# untitled.net
KiCad netlist of a schematic drawn in EAGLE
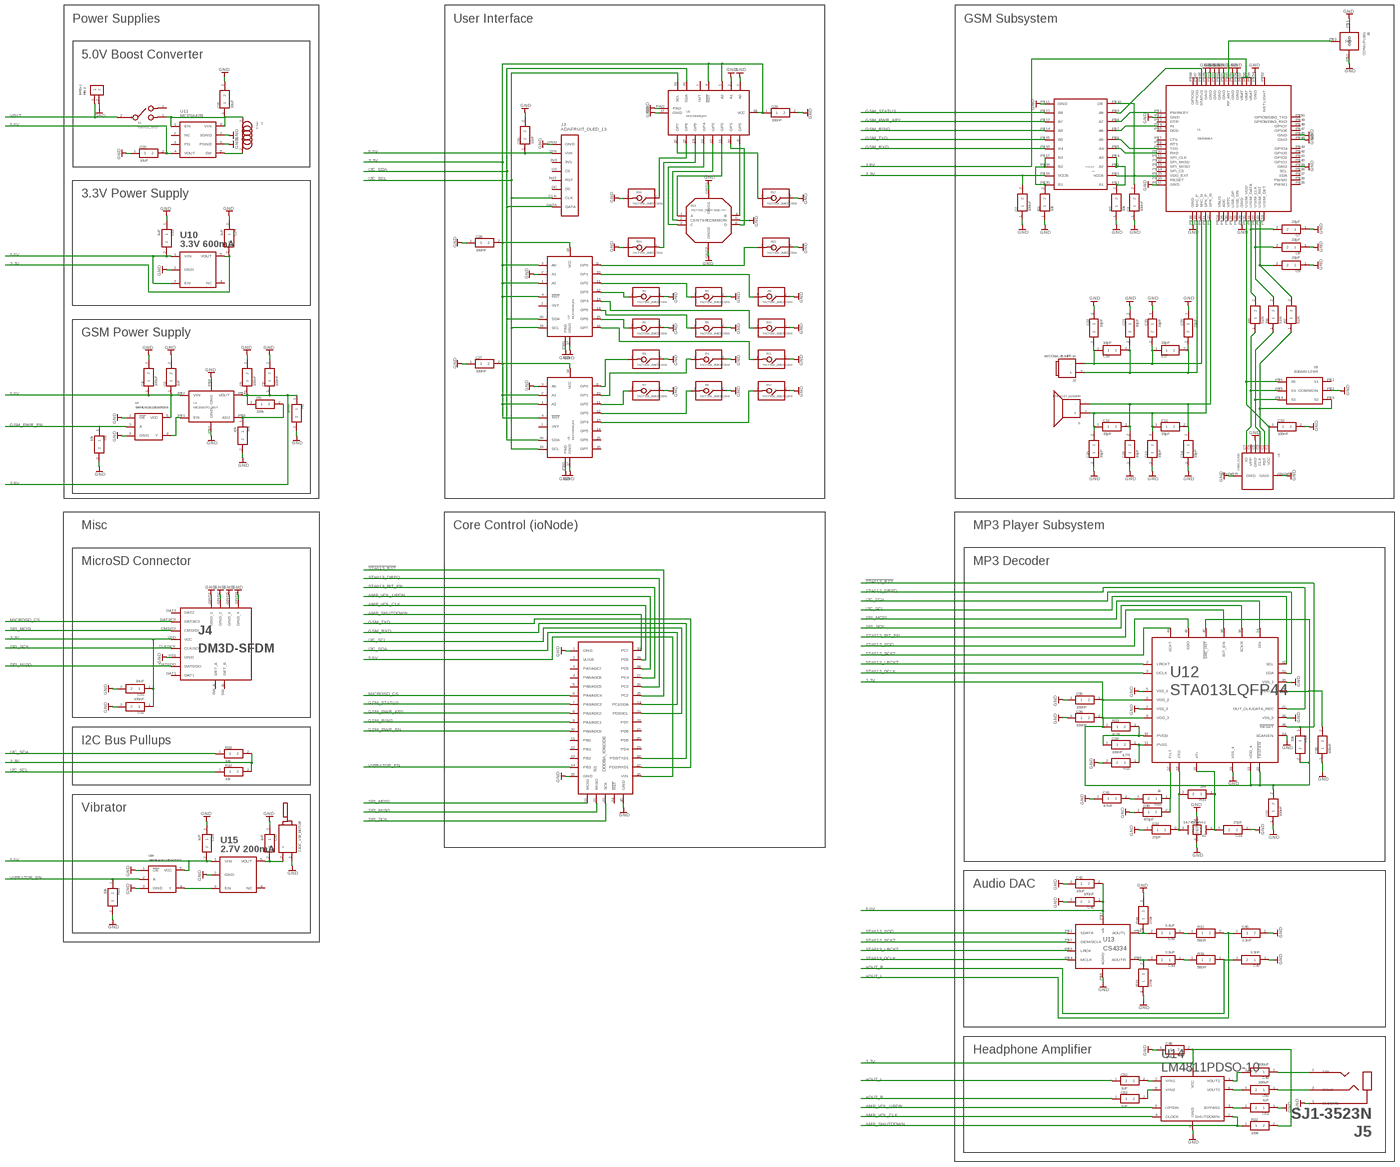
[diagram p0: schematic, sheet 1, overview]
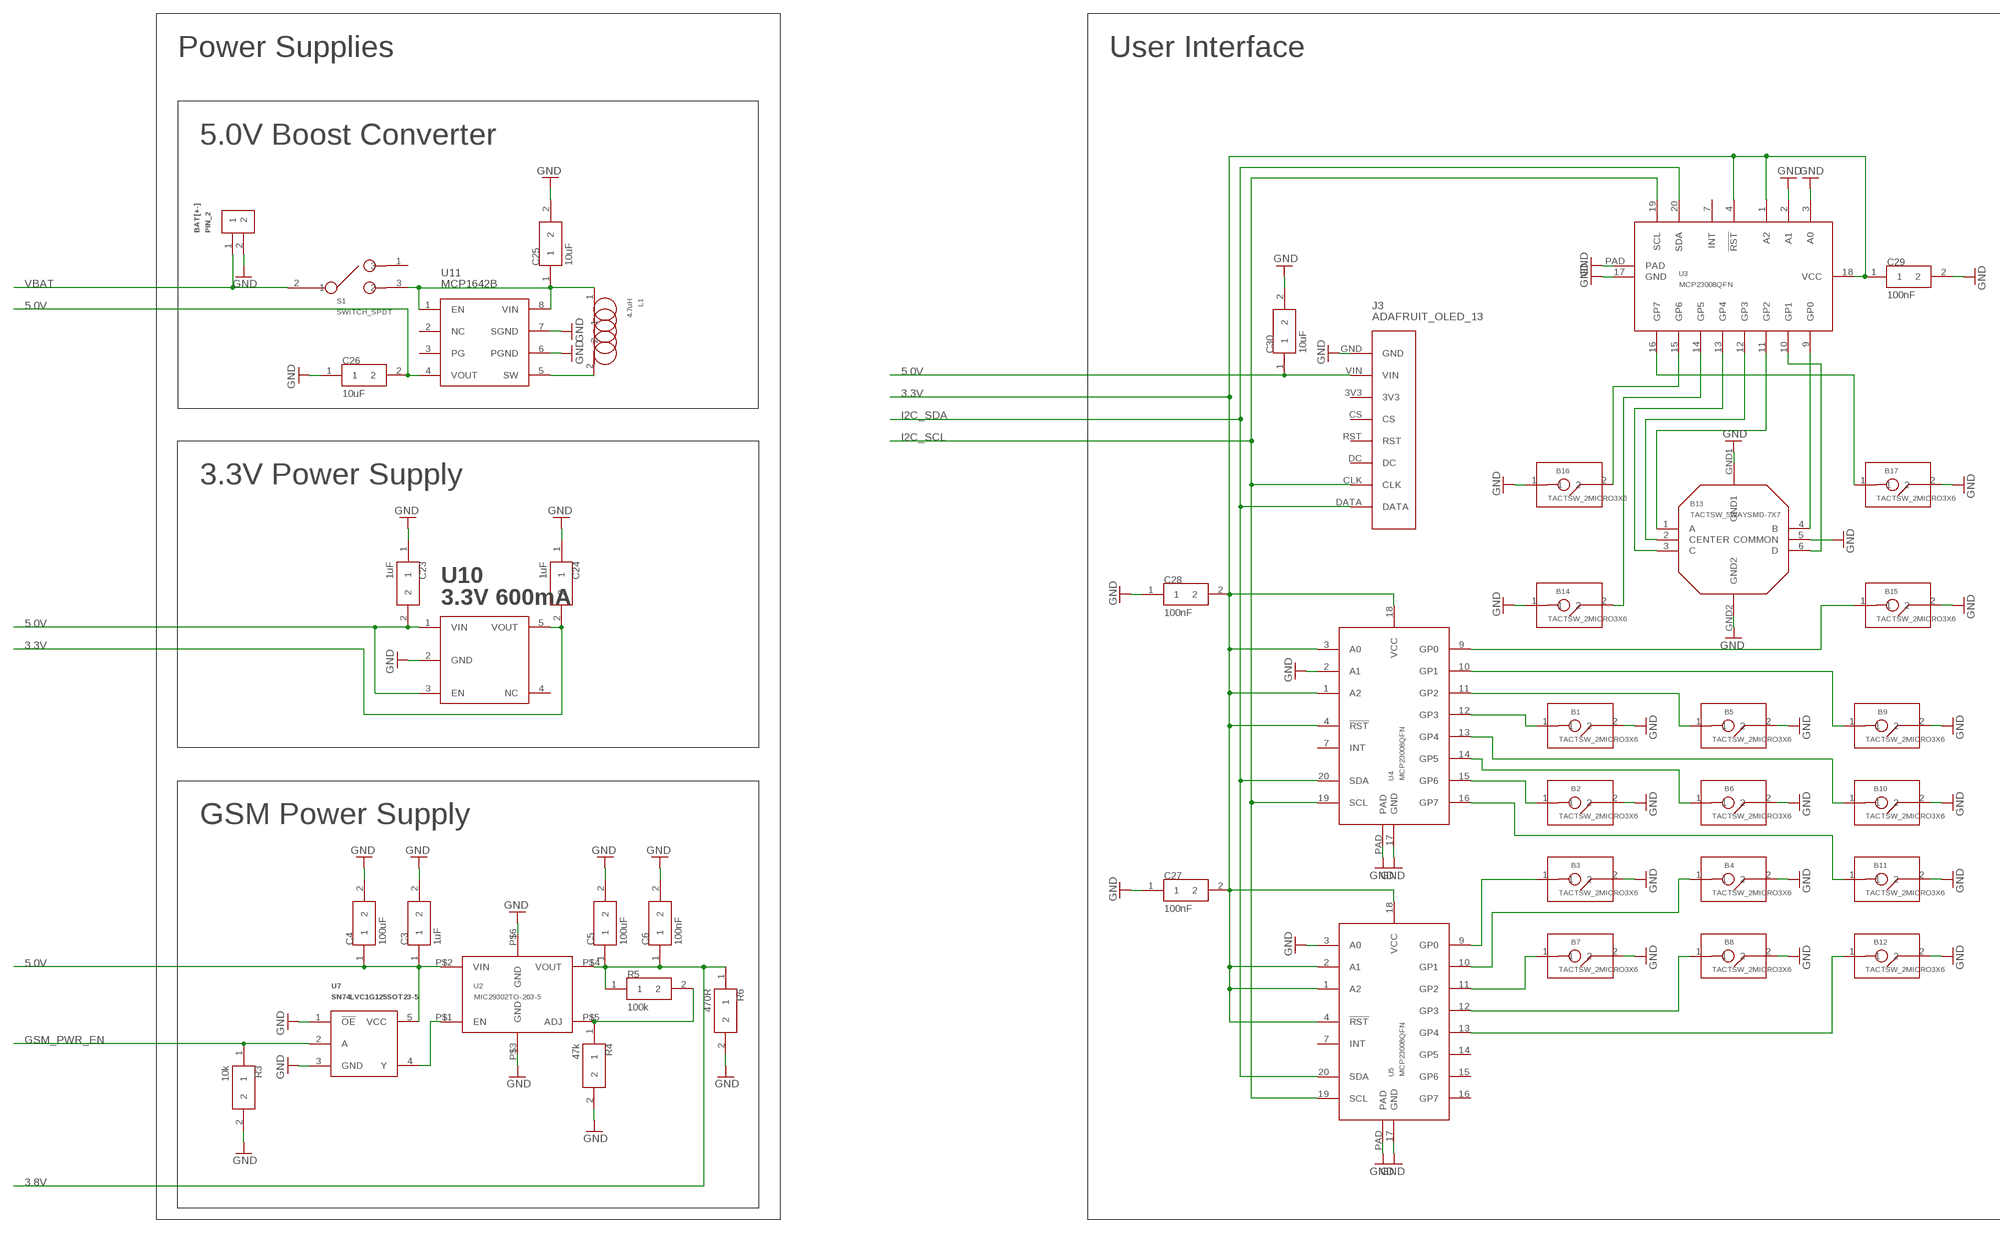
[diagram p1: schematic, sheet 1, part 1 of 4]
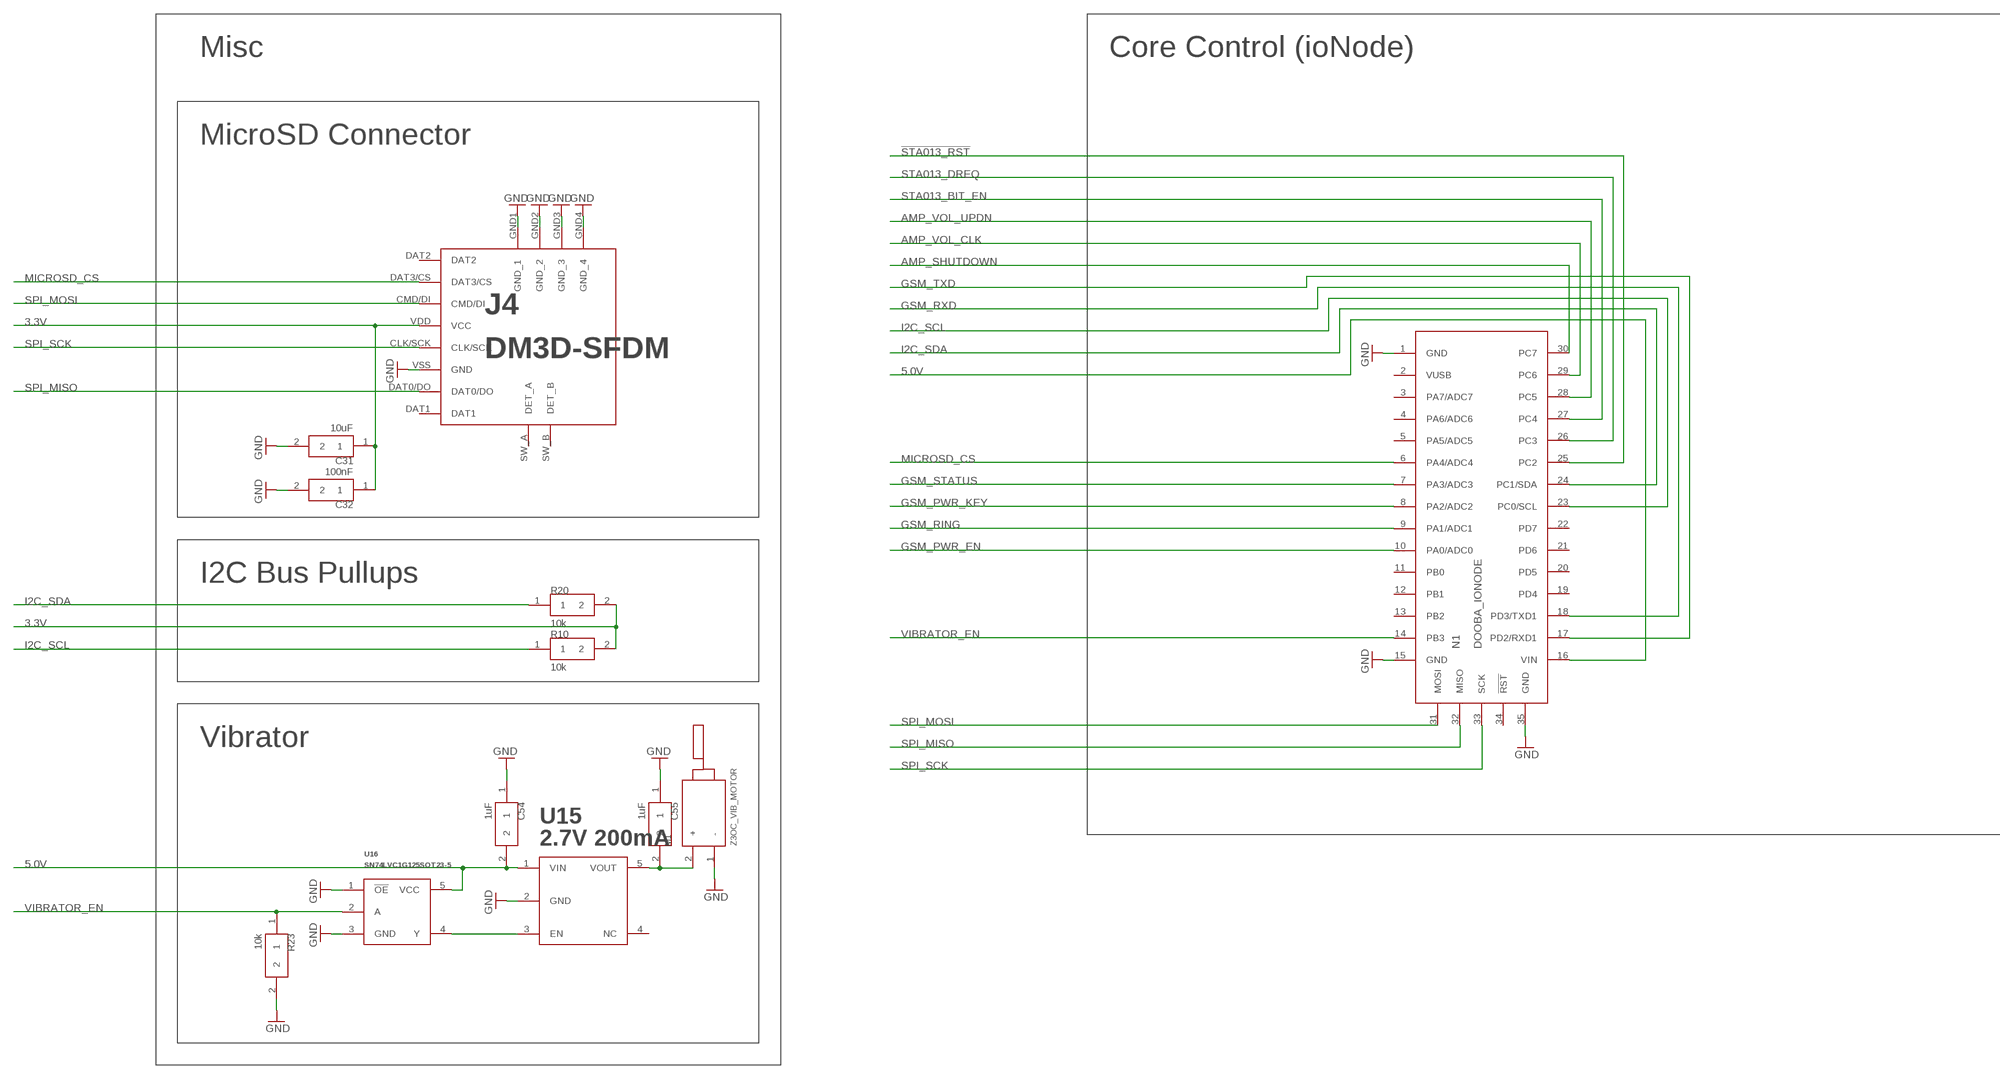
[diagram p2: schematic, sheet 1, part 2 of 4]
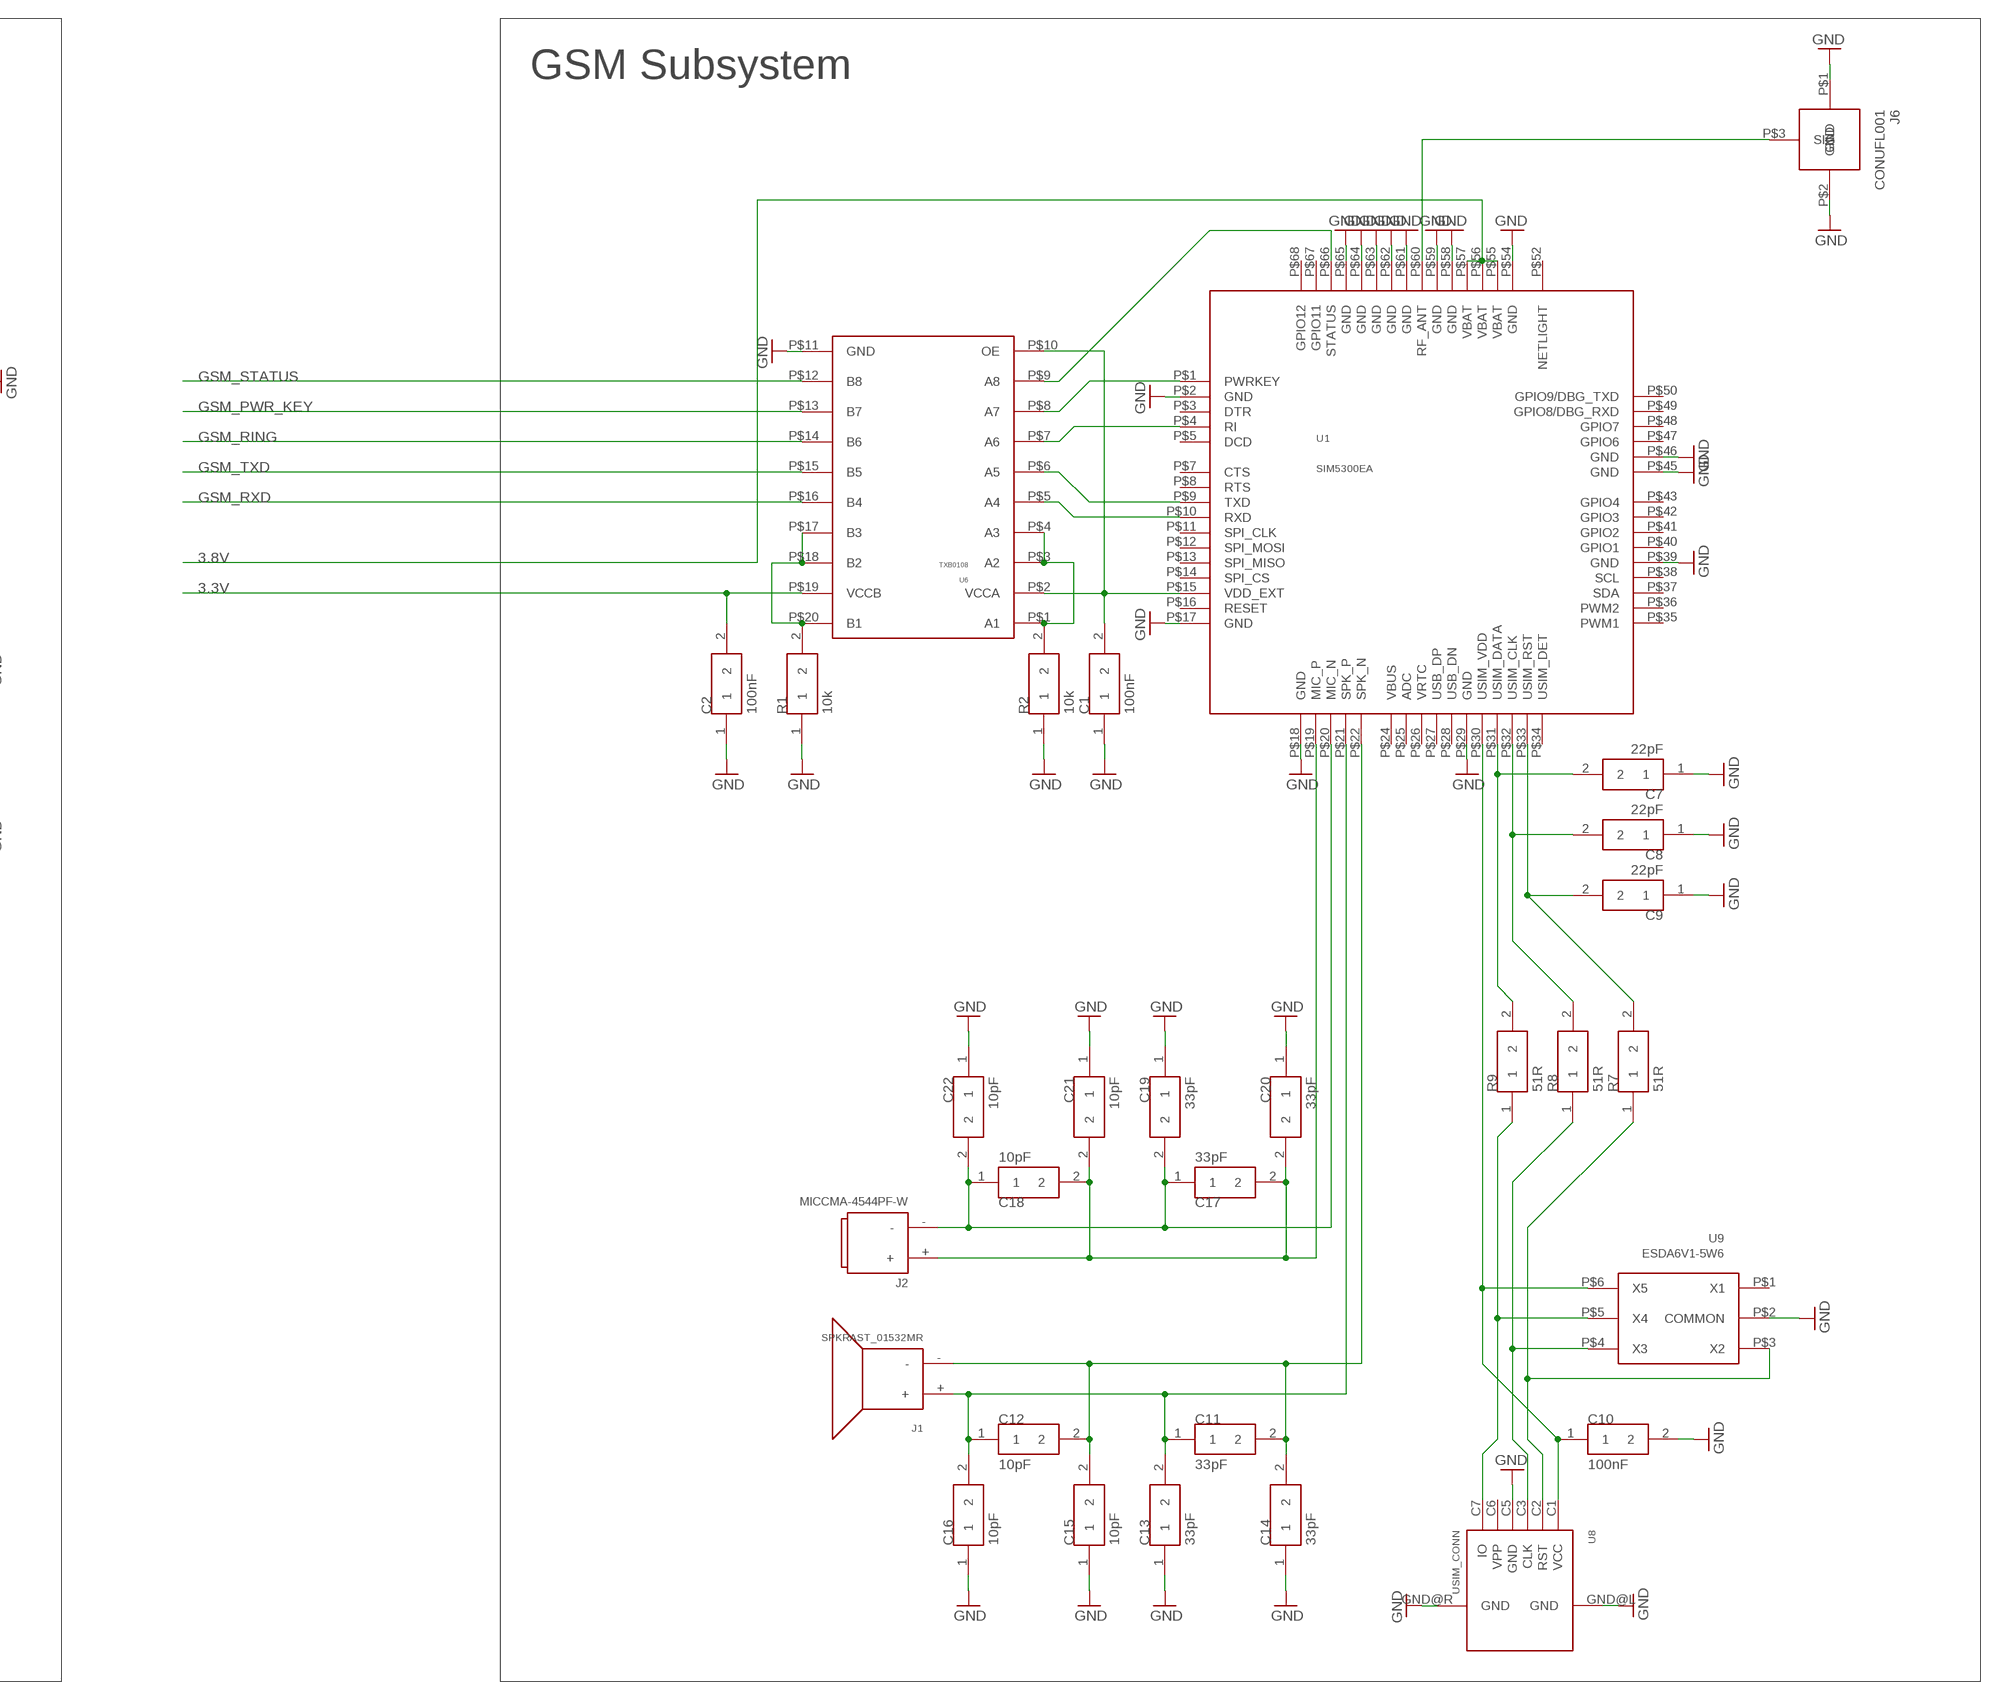
[diagram p3: schematic, sheet 1, part 3 of 4]
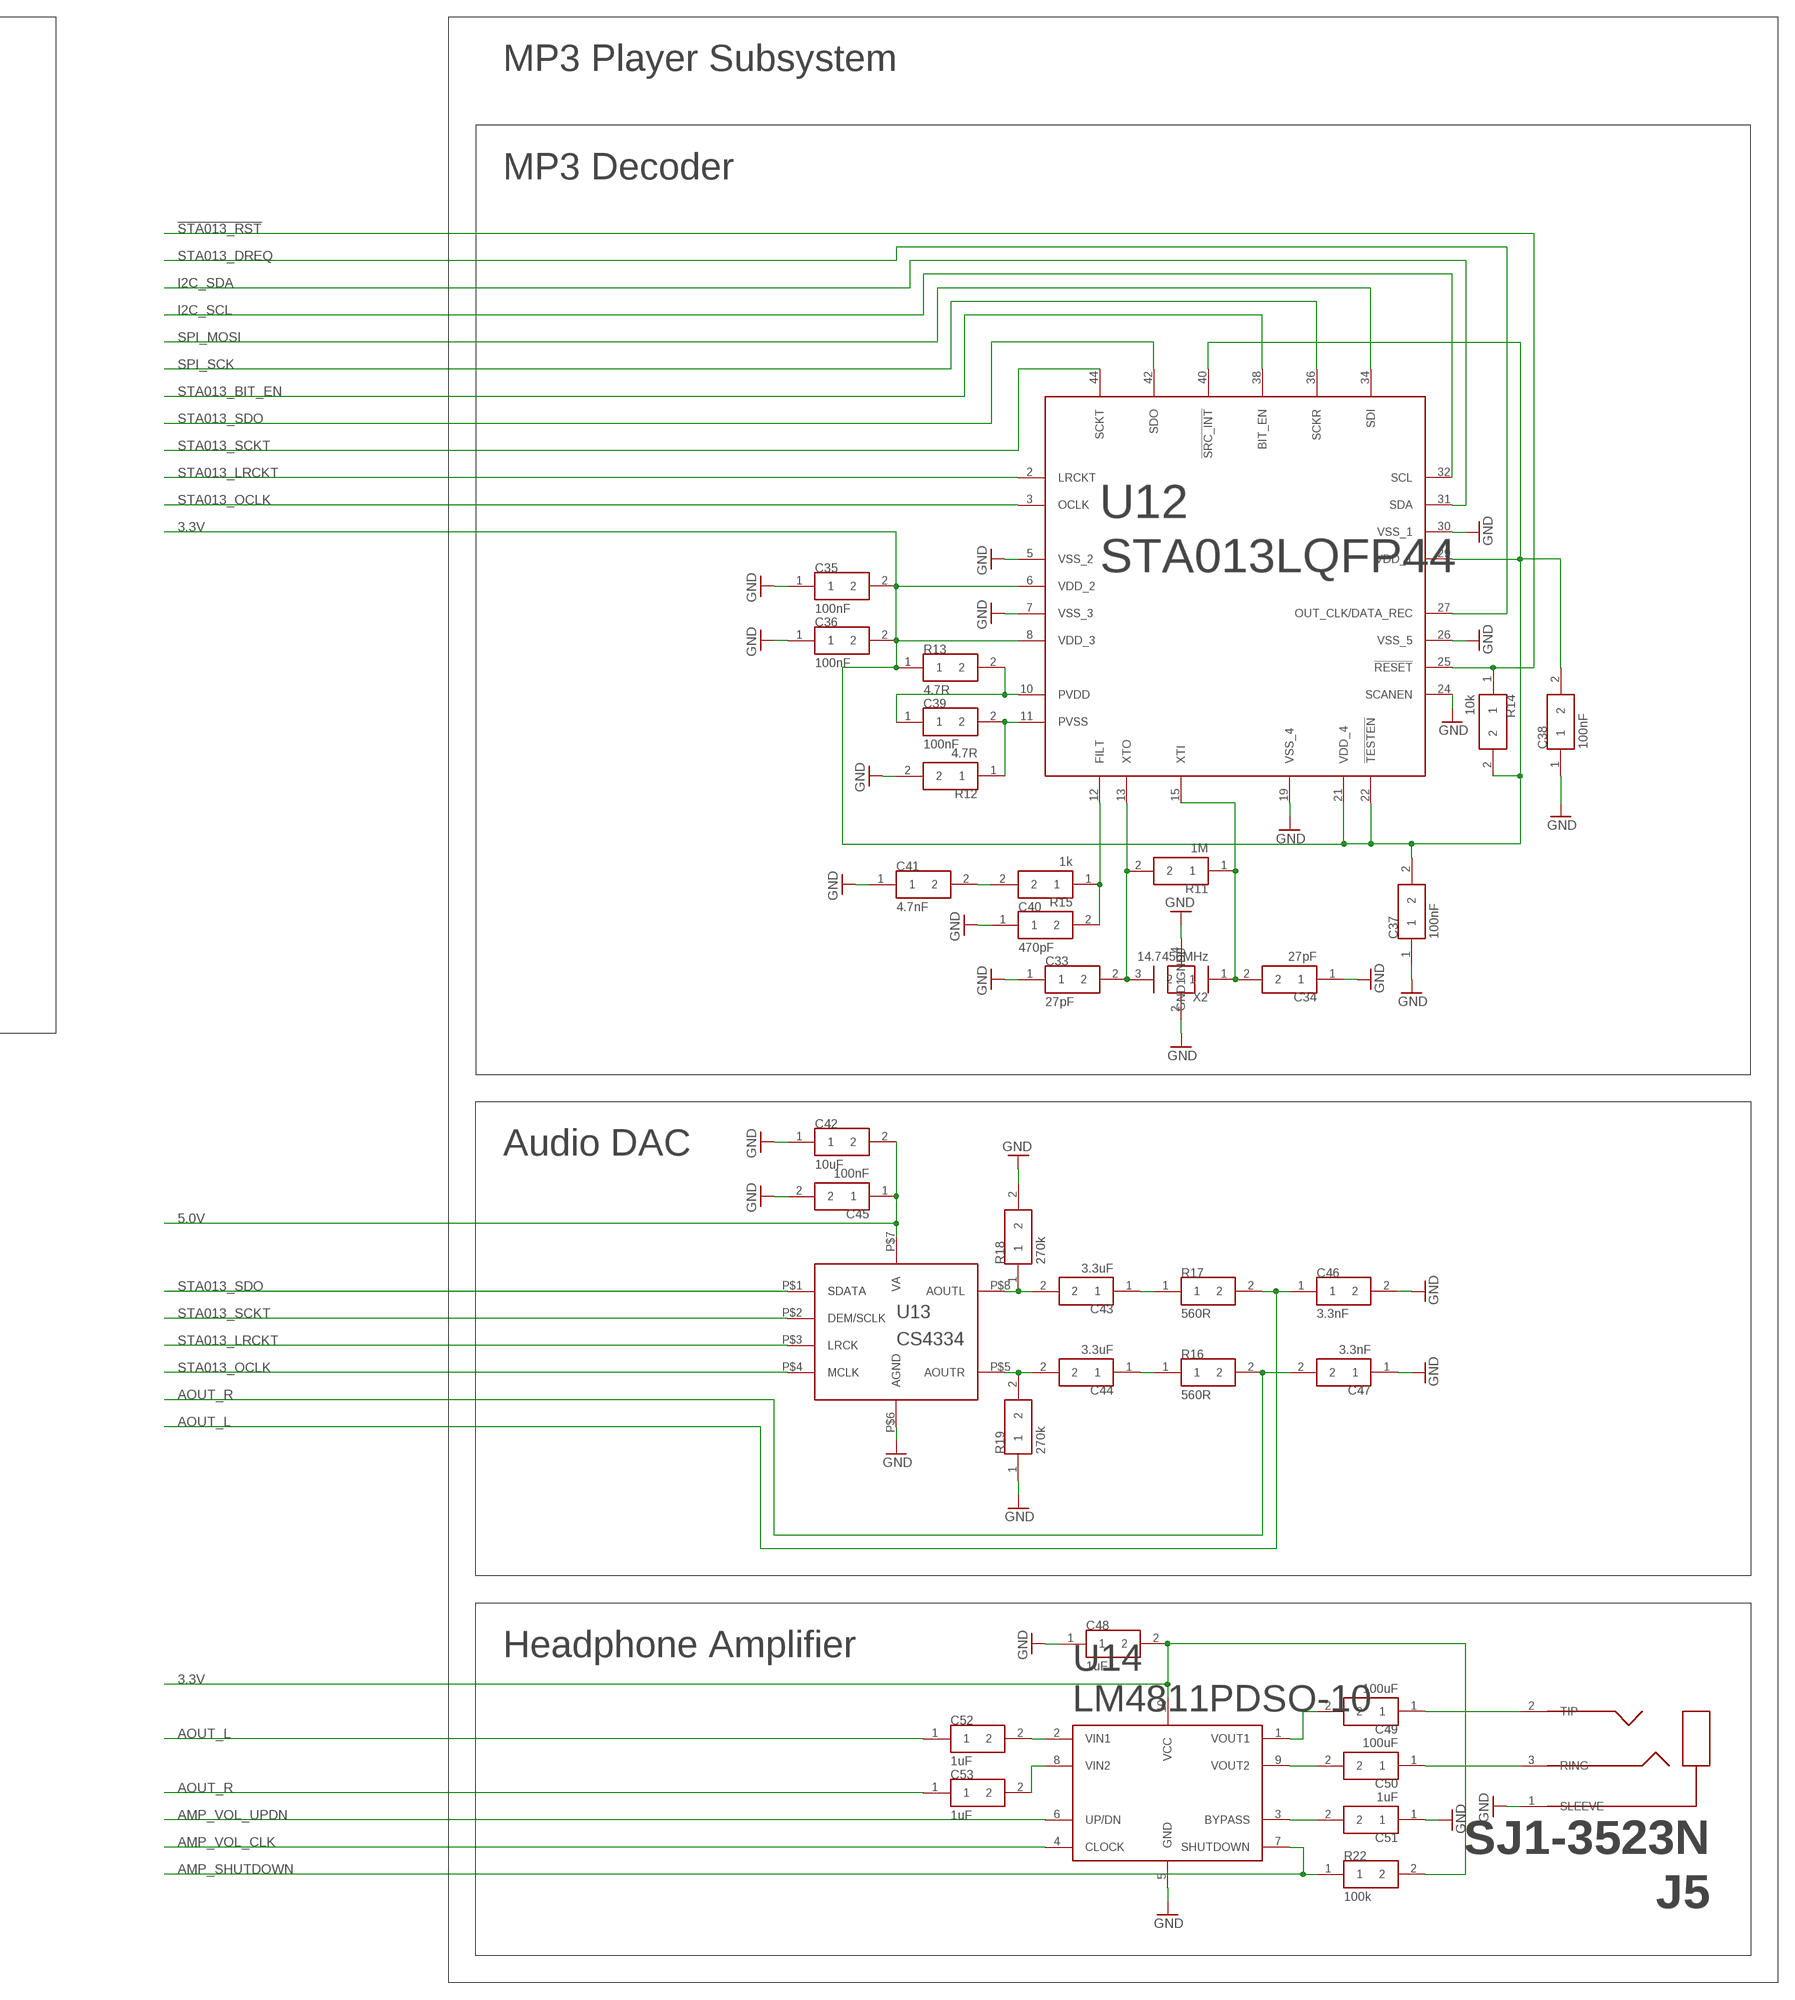
[diagram p4: schematic, sheet 1, part 4 of 4]

(export (version "E")
  (design (tool "Eeschema 10.0.6"))
  (components
    (comp (ref "B1")
      (value "TACTSW_2MICRO3X6")
      (footprint "eagle-import:TACTSW_MICRO3X6")
      (libsource (lib "eagle-import") (part "TACTSW_2MICRO3X6"))
    )
    (comp (ref "B2")
      (value "TACTSW_2MICRO3X6")
      (footprint "eagle-import:TACTSW_MICRO3X6")
      (libsource (lib "eagle-import") (part "TACTSW_2MICRO3X6"))
    )
    (comp (ref "B3")
      (value "TACTSW_2MICRO3X6")
      (footprint "eagle-import:TACTSW_MICRO3X6")
      (libsource (lib "eagle-import") (part "TACTSW_2MICRO3X6"))
    )
    (comp (ref "B4")
      (value "TACTSW_2MICRO3X6")
      (footprint "eagle-import:TACTSW_MICRO3X6")
      (libsource (lib "eagle-import") (part "TACTSW_2MICRO3X6"))
    )
    (comp (ref "B5")
      (value "TACTSW_2MICRO3X6")
      (footprint "eagle-import:TACTSW_MICRO3X6")
      (libsource (lib "eagle-import") (part "TACTSW_2MICRO3X6"))
    )
    (comp (ref "B6")
      (value "TACTSW_2MICRO3X6")
      (footprint "eagle-import:TACTSW_MICRO3X6")
      (libsource (lib "eagle-import") (part "TACTSW_2MICRO3X6"))
    )
    (comp (ref "B7")
      (value "TACTSW_2MICRO3X6")
      (footprint "eagle-import:TACTSW_MICRO3X6")
      (libsource (lib "eagle-import") (part "TACTSW_2MICRO3X6"))
    )
    (comp (ref "B8")
      (value "TACTSW_2MICRO3X6")
      (footprint "eagle-import:TACTSW_MICRO3X6")
      (libsource (lib "eagle-import") (part "TACTSW_2MICRO3X6"))
    )
    (comp (ref "B9")
      (value "TACTSW_2MICRO3X6")
      (footprint "eagle-import:TACTSW_MICRO3X6")
      (libsource (lib "eagle-import") (part "TACTSW_2MICRO3X6"))
    )
    (comp (ref "B10")
      (value "TACTSW_2MICRO3X6")
      (footprint "eagle-import:TACTSW_MICRO3X6")
      (libsource (lib "eagle-import") (part "TACTSW_2MICRO3X6"))
    )
    (comp (ref "B11")
      (value "TACTSW_2MICRO3X6")
      (footprint "eagle-import:TACTSW_MICRO3X6")
      (libsource (lib "eagle-import") (part "TACTSW_2MICRO3X6"))
    )
    (comp (ref "B12")
      (value "TACTSW_2MICRO3X6")
      (footprint "eagle-import:TACTSW_MICRO3X6")
      (libsource (lib "eagle-import") (part "TACTSW_2MICRO3X6"))
    )
    (comp (ref "B13")
      (value "TACTSW_5WAYSMD-7X7")
      (footprint "eagle-import:TACTSW-5WAY-7X7")
      (libsource (lib "eagle-import") (part "TACTSW_5WAYSMD-7X7"))
    )
    (comp (ref "B14")
      (value "TACTSW_2MICRO3X6")
      (footprint "eagle-import:TACTSW_MICRO3X6")
      (libsource (lib "eagle-import") (part "TACTSW_2MICRO3X6"))
    )
    (comp (ref "B15")
      (value "TACTSW_2MICRO3X6")
      (footprint "eagle-import:TACTSW_MICRO3X6")
      (libsource (lib "eagle-import") (part "TACTSW_2MICRO3X6"))
    )
    (comp (ref "B16")
      (value "TACTSW_2MICRO3X6")
      (footprint "eagle-import:TACTSW_MICRO3X6")
      (libsource (lib "eagle-import") (part "TACTSW_2MICRO3X6"))
    )
    (comp (ref "B17")
      (value "TACTSW_2MICRO3X6")
      (footprint "eagle-import:TACTSW_MICRO3X6")
      (libsource (lib "eagle-import") (part "TACTSW_2MICRO3X6"))
    )
    (comp (ref "BAT[+-]")
      (value "PIN_2")
      (footprint "eagle-import:PIN_2")
      (libsource (lib "eagle-import") (part "PIN_2"))
    )
    (comp (ref "C1")
      (value "100nF")
      (footprint "eagle-import:0805")
      (libsource (lib "eagle-import") (part "CAP0805"))
    )
    (comp (ref "C2")
      (value "100nF")
      (footprint "eagle-import:0805")
      (libsource (lib "eagle-import") (part "CAP0805"))
    )
    (comp (ref "C3")
      (value "1uF")
      (footprint "eagle-import:0805")
      (libsource (lib "eagle-import") (part "CAP0805"))
    )
    (comp (ref "C4")
      (value "100uF")
      (footprint "eagle-import:1210")
      (libsource (lib "eagle-import") (part "CAP1210"))
    )
    (comp (ref "C5")
      (value "100uF")
      (footprint "eagle-import:1210")
      (libsource (lib "eagle-import") (part "CAP1210"))
    )
    (comp (ref "C6")
      (value "100nF")
      (footprint "eagle-import:0805")
      (libsource (lib "eagle-import") (part "CAP0805"))
    )
    (comp (ref "C7")
      (value "22pF")
      (footprint "eagle-import:0805")
      (libsource (lib "eagle-import") (part "CAP0805"))
    )
    (comp (ref "C8")
      (value "22pF")
      (footprint "eagle-import:0805")
      (libsource (lib "eagle-import") (part "CAP0805"))
    )
    (comp (ref "C9")
      (value "22pF")
      (footprint "eagle-import:0805")
      (libsource (lib "eagle-import") (part "CAP0805"))
    )
    (comp (ref "C10")
      (value "100nF")
      (footprint "eagle-import:0805")
      (libsource (lib "eagle-import") (part "CAP0805"))
    )
    (comp (ref "C11")
      (value "33pF")
      (footprint "eagle-import:0805")
      (libsource (lib "eagle-import") (part "CAP0805"))
    )
    (comp (ref "C12")
      (value "10pF")
      (footprint "eagle-import:0805")
      (libsource (lib "eagle-import") (part "CAP0805"))
    )
    (comp (ref "C13")
      (value "33pF")
      (footprint "eagle-import:0805")
      (libsource (lib "eagle-import") (part "CAP0805"))
    )
    (comp (ref "C14")
      (value "33pF")
      (footprint "eagle-import:0805")
      (libsource (lib "eagle-import") (part "CAP0805"))
    )
    (comp (ref "C15")
      (value "10pF")
      (footprint "eagle-import:0805")
      (libsource (lib "eagle-import") (part "CAP0805"))
    )
    (comp (ref "C16")
      (value "10pF")
      (footprint "eagle-import:0805")
      (libsource (lib "eagle-import") (part "CAP0805"))
    )
    (comp (ref "C17")
      (value "33pF")
      (footprint "eagle-import:0805")
      (libsource (lib "eagle-import") (part "CAP0805"))
    )
    (comp (ref "C18")
      (value "10pF")
      (footprint "eagle-import:0805")
      (libsource (lib "eagle-import") (part "CAP0805"))
    )
    (comp (ref "C19")
      (value "33pF")
      (footprint "eagle-import:0805")
      (libsource (lib "eagle-import") (part "CAP0805"))
    )
    (comp (ref "C20")
      (value "33pF")
      (footprint "eagle-import:0805")
      (libsource (lib "eagle-import") (part "CAP0805"))
    )
    (comp (ref "C21")
      (value "10pF")
      (footprint "eagle-import:0805")
      (libsource (lib "eagle-import") (part "CAP0805"))
    )
    (comp (ref "C22")
      (value "10pF")
      (footprint "eagle-import:0805")
      (libsource (lib "eagle-import") (part "CAP0805"))
    )
    (comp (ref "C23")
      (value "1uF")
      (footprint "eagle-import:0805")
      (libsource (lib "eagle-import") (part "CAP0805"))
    )
    (comp (ref "C24")
      (value "1uF")
      (footprint "eagle-import:0805")
      (libsource (lib "eagle-import") (part "CAP0805"))
    )
    (comp (ref "C25")
      (value "10uF")
      (footprint "eagle-import:0805")
      (libsource (lib "eagle-import") (part "CAP0805"))
    )
    (comp (ref "C26")
      (value "10uF")
      (footprint "eagle-import:0805")
      (libsource (lib "eagle-import") (part "CAP0805"))
    )
    (comp (ref "C27")
      (value "100nF")
      (footprint "eagle-import:0805")
      (libsource (lib "eagle-import") (part "CAP0805"))
    )
    (comp (ref "C28")
      (value "100nF")
      (footprint "eagle-import:0805")
      (libsource (lib "eagle-import") (part "CAP0805"))
    )
    (comp (ref "C29")
      (value "100nF")
      (footprint "eagle-import:0805")
      (libsource (lib "eagle-import") (part "CAP0805"))
    )
    (comp (ref "C30")
      (value "10uF")
      (footprint "eagle-import:0805")
      (libsource (lib "eagle-import") (part "CAP0805"))
    )
    (comp (ref "C31")
      (value "10uF")
      (footprint "eagle-import:0805")
      (libsource (lib "eagle-import") (part "CAP0805"))
    )
    (comp (ref "C32")
      (value "100nF")
      (footprint "eagle-import:0805")
      (libsource (lib "eagle-import") (part "CAP0805"))
    )
    (comp (ref "C33")
      (value "27pF")
      (footprint "eagle-import:0805")
      (libsource (lib "eagle-import") (part "CAP0805"))
    )
    (comp (ref "C34")
      (value "27pF")
      (footprint "eagle-import:0805")
      (libsource (lib "eagle-import") (part "CAP0805"))
    )
    (comp (ref "C35")
      (value "100nF")
      (footprint "eagle-import:0805")
      (libsource (lib "eagle-import") (part "CAP0805"))
    )
    (comp (ref "C36")
      (value "100nF")
      (footprint "eagle-import:0805")
      (libsource (lib "eagle-import") (part "CAP0805"))
    )
    (comp (ref "C37")
      (value "100nF")
      (footprint "eagle-import:0805")
      (libsource (lib "eagle-import") (part "CAP0805"))
    )
    (comp (ref "C38")
      (value "100nF")
      (footprint "eagle-import:0805")
      (libsource (lib "eagle-import") (part "CAP0805"))
    )
    (comp (ref "C39")
      (value "100nF")
      (footprint "eagle-import:0805")
      (libsource (lib "eagle-import") (part "CAP0805"))
    )
    (comp (ref "C40")
      (value "470pF")
      (footprint "eagle-import:0805")
      (libsource (lib "eagle-import") (part "CAP0805"))
    )
    (comp (ref "C41")
      (value "4.7nF")
      (footprint "eagle-import:0805")
      (libsource (lib "eagle-import") (part "CAP0805"))
    )
    (comp (ref "C42")
      (value "10uF")
      (footprint "eagle-import:0805")
      (libsource (lib "eagle-import") (part "CAP0805"))
    )
    (comp (ref "C43")
      (value "3.3uF")
      (footprint "eagle-import:0805")
      (libsource (lib "eagle-import") (part "CAP0805"))
    )
    (comp (ref "C44")
      (value "3.3uF")
      (footprint "eagle-import:0805")
      (libsource (lib "eagle-import") (part "CAP0805"))
    )
    (comp (ref "C45")
      (value "100nF")
      (footprint "eagle-import:0805")
      (libsource (lib "eagle-import") (part "CAP0805"))
    )
    (comp (ref "C46")
      (value "3.3nF")
      (footprint "eagle-import:0805")
      (libsource (lib "eagle-import") (part "CAP0805"))
    )
    (comp (ref "C47")
      (value "3.3nF")
      (footprint "eagle-import:0805")
      (libsource (lib "eagle-import") (part "CAP0805"))
    )
    (comp (ref "C48")
      (value "1uF")
      (footprint "eagle-import:0805")
      (libsource (lib "eagle-import") (part "CAP0805"))
    )
    (comp (ref "C49")
      (value "100uF")
      (footprint "eagle-import:1210")
      (libsource (lib "eagle-import") (part "CAP1210"))
    )
    (comp (ref "C50")
      (value "100uF")
      (footprint "eagle-import:1210")
      (libsource (lib "eagle-import") (part "CAP1210"))
    )
    (comp (ref "C51")
      (value "1uF")
      (footprint "eagle-import:0805")
      (libsource (lib "eagle-import") (part "CAP0805"))
    )
    (comp (ref "C52")
      (value "1uF")
      (footprint "eagle-import:0805")
      (libsource (lib "eagle-import") (part "CAP0805"))
    )
    (comp (ref "C53")
      (value "1uF")
      (footprint "eagle-import:0805")
      (libsource (lib "eagle-import") (part "CAP0805"))
    )
    (comp (ref "C54")
      (value "1uF")
      (footprint "eagle-import:0805")
      (libsource (lib "eagle-import") (part "CAP0805"))
    )
    (comp (ref "C55")
      (value "1uF")
      (footprint "eagle-import:0805")
      (libsource (lib "eagle-import") (part "CAP0805"))
    )
    (comp (ref "J1")
      (value "SPKRAST_01532MR")
      (footprint "eagle-import:SPKR_AST_01532MR")
      (libsource (lib "eagle-import") (part "SPKRAST_01532MR"))
    )
    (comp (ref "J2")
      (value "MICCMA-4544PF-W")
      (footprint "eagle-import:MIC_CMA-4544PF-W")
      (libsource (lib "eagle-import") (part "MICCMA-4544PF-W"))
    )
    (comp (ref "J3")
      (value "ADAFRUIT_OLED_13")
      (footprint "eagle-import:ADAFRUIT_OLED_13")
      (libsource (lib "eagle-import") (part "ADAFRUIT_OLED_13"))
    )
    (comp (ref "J4")
      (value "DM3D-SFDM")
      (footprint "eagle-import:DM3D-SF")
      (libsource (lib "eagle-import") (part "DM3D-SFDM"))
    )
    (comp (ref "J5")
      (value "SJ1-3523N")
      (footprint "eagle-import:SJ1-352XN")
      (libsource (lib "eagle-import") (part "SJ1-3523N"))
    )
    (comp (ref "J6")
      (value "CONUFL001")
      (footprint "eagle-import:CONUFL001")
      (libsource (lib "eagle-import") (part "CONUFL001"))
    )
    (comp (ref "L1")
      (value "4.7uH")
      (footprint "eagle-import:2520")
      (libsource (lib "eagle-import") (part "IND2520"))
    )
    (comp (ref "M1")
      (value "Z3OC_VIB_MOTOR")
      (footprint "eagle-import:Z3OC_VIB_MOTOR")
      (libsource (lib "eagle-import") (part "Z3OC_VIB_MOTOR"))
    )
    (comp (ref "N1")
      (value "DOOBA_IONODE")
      (footprint "eagle-import:DOOBA_IONODE")
      (libsource (lib "eagle-import") (part "DOOBA_IONODE"))
    )
    (comp (ref "R1")
      (value "10k")
      (footprint "eagle-import:0805")
      (libsource (lib "eagle-import") (part "RES0805"))
    )
    (comp (ref "R2")
      (value "10k")
      (footprint "eagle-import:0805")
      (libsource (lib "eagle-import") (part "RES0805"))
    )
    (comp (ref "R3")
      (value "10k")
      (footprint "eagle-import:0805")
      (libsource (lib "eagle-import") (part "RES0805"))
    )
    (comp (ref "R4")
      (value "47k")
      (footprint "eagle-import:0805")
      (libsource (lib "eagle-import") (part "RES0805"))
    )
    (comp (ref "R5")
      (value "100k")
      (footprint "eagle-import:0805")
      (libsource (lib "eagle-import") (part "RES0805"))
    )
    (comp (ref "R6")
      (value "470R")
      (footprint "eagle-import:0805")
      (libsource (lib "eagle-import") (part "RES0805"))
    )
    (comp (ref "R7")
      (value "51R")
      (footprint "eagle-import:0805")
      (libsource (lib "eagle-import") (part "RES0805"))
    )
    (comp (ref "R8")
      (value "51R")
      (footprint "eagle-import:0805")
      (libsource (lib "eagle-import") (part "RES0805"))
    )
    (comp (ref "R9")
      (value "51R")
      (footprint "eagle-import:0805")
      (libsource (lib "eagle-import") (part "RES0805"))
    )
    (comp (ref "R10")
      (value "10k")
      (footprint "eagle-import:0805")
      (libsource (lib "eagle-import") (part "RES0805"))
    )
    (comp (ref "R11")
      (value "1M")
      (footprint "eagle-import:0805")
      (libsource (lib "eagle-import") (part "RES0805"))
    )
    (comp (ref "R12")
      (value "4.7R")
      (footprint "eagle-import:0805")
      (libsource (lib "eagle-import") (part "RES0805"))
    )
    (comp (ref "R13")
      (value "4.7R")
      (footprint "eagle-import:0805")
      (libsource (lib "eagle-import") (part "RES0805"))
    )
    (comp (ref "R14")
      (value "10k")
      (footprint "eagle-import:0805")
      (libsource (lib "eagle-import") (part "RES0805"))
    )
    (comp (ref "R15")
      (value "1k")
      (footprint "eagle-import:0805")
      (libsource (lib "eagle-import") (part "RES0805"))
    )
    (comp (ref "R16")
      (value "560R")
      (footprint "eagle-import:0805")
      (libsource (lib "eagle-import") (part "RES0805"))
    )
    (comp (ref "R17")
      (value "560R")
      (footprint "eagle-import:0805")
      (libsource (lib "eagle-import") (part "RES0805"))
    )
    (comp (ref "R18")
      (value "270k")
      (footprint "eagle-import:0805")
      (libsource (lib "eagle-import") (part "RES0805"))
    )
    (comp (ref "R19")
      (value "270k")
      (footprint "eagle-import:0805")
      (libsource (lib "eagle-import") (part "RES0805"))
    )
    (comp (ref "R20")
      (value "10k")
      (footprint "eagle-import:0805")
      (libsource (lib "eagle-import") (part "RES0805"))
    )
    (comp (ref "R22")
      (value "100k")
      (footprint "eagle-import:0805")
      (libsource (lib "eagle-import") (part "RES0805"))
    )
    (comp (ref "R23")
      (value "10k")
      (footprint "eagle-import:0805")
      (libsource (lib "eagle-import") (part "RES0805"))
    )
    (comp (ref "S1")
      (value "SWITCH_SPDT")
      (footprint "eagle-import:JS102011")
      (libsource (lib "eagle-import") (part "SWITCH_SPDT"))
    )
    (comp (ref "U1")
      (value "SIM5300EA")
      (footprint "eagle-import:SIM5300")
      (libsource (lib "eagle-import") (part "SIM5300EA"))
    )
    (comp (ref "U2")
      (value "MIC29302TO-263-5")
      (footprint "eagle-import:TO-263")
      (libsource (lib "eagle-import") (part "MIC29302TO-263-5"))
    )
    (comp (ref "U3")
      (value "MCP23008QFN")
      (footprint "eagle-import:20-VQFN")
      (libsource (lib "eagle-import") (part "MCP23008QFN"))
    )
    (comp (ref "U4")
      (value "MCP23008QFN")
      (footprint "eagle-import:20-VQFN")
      (libsource (lib "eagle-import") (part "MCP23008QFN"))
    )
    (comp (ref "U5")
      (value "MCP23008QFN")
      (footprint "eagle-import:20-VQFN")
      (libsource (lib "eagle-import") (part "MCP23008QFN"))
    )
    (comp (ref "U6")
      (value "TXB0108")
      (footprint "eagle-import:TSSOP-20")
      (libsource (lib "eagle-import") (part "TXB0108"))
    )
    (comp (ref "U7")
      (value "SN74LVC1G125SOT23-5")
      (footprint "eagle-import:SOT23-5")
      (libsource (lib "eagle-import") (part "SN74LVC1G125SOT23-5"))
    )
    (comp (ref "U8")
      (value "USIM_CONN")
      (footprint "eagle-import:WE_USIM_HINGE")
      (libsource (lib "eagle-import") (part "USIM_CONN"))
    )
    (comp (ref "U9")
      (value "ESDA6V1-5W6")
      (footprint "eagle-import:SOT-323-6L")
      (libsource (lib "eagle-import") (part "ESDA6V1-5W6"))
    )
    (comp (ref "U10")
      (value "3.3V 600mA")
      (footprint "eagle-import:SOT23-5")
      (libsource (lib "eagle-import") (part "LP3985SOT23-5"))
    )
    (comp (ref "U11")
      (value "MCP1642B")
      (footprint "eagle-import:MSOP8")
      (libsource (lib "eagle-import") (part "MCP1642B"))
    )
    (comp (ref "U12")
      (value "STA013LQFP44")
      (footprint "eagle-import:QFP44")
      (libsource (lib "eagle-import") (part "STA013LQFP44"))
    )
    (comp (ref "U13")
      (value "CS4334")
      (footprint "eagle-import:SO8")
      (libsource (lib "eagle-import") (part "CS4334"))
    )
    (comp (ref "U14")
      (value "LM4811PDSO-10")
      (footprint "eagle-import:PDSO-10")
      (libsource (lib "eagle-import") (part "LM4811PDSO-10"))
    )
    (comp (ref "U15")
      (value "2.7V 200mA")
      (footprint "eagle-import:SOT23-5")
      (libsource (lib "eagle-import") (part "LP3985SOT23-5"))
    )
    (comp (ref "U16")
      (value "SN74LVC1G125SOT23-5")
      (footprint "eagle-import:SOT23-5")
      (libsource (lib "eagle-import") (part "SN74LVC1G125SOT23-5"))
    )
    (comp (ref "X2")
      (value "14.7456MHz")
      (footprint "eagle-import:XTAL_3225")
      (libsource (lib "eagle-import") (part "XTAL_GNDSMD_3225"))
    )
  )
  (nets
    (net (code "1") (name "/3.3V") (class "Default")
      (node (ref "C2") (pin "2") (pinfunction "2_2") (pintype "bidirectional"))
      (node (ref "C24") (pin "2") (pinfunction "2_2") (pintype "bidirectional"))
      (node (ref "C27") (pin "2") (pinfunction "2_2") (pintype "bidirectional"))
      (node (ref "C28") (pin "2") (pinfunction "2_2") (pintype "bidirectional"))
      (node (ref "C29") (pin "1") (pinfunction "1_1") (pintype "bidirectional"))
      (node (ref "C31") (pin "1") (pinfunction "1_1") (pintype "bidirectional"))
      (node (ref "C32") (pin "1") (pinfunction "1_1") (pintype "bidirectional"))
      (node (ref "C35") (pin "2") (pinfunction "2_2") (pintype "bidirectional"))
      (node (ref "C36") (pin "2") (pinfunction "2_2") (pintype "bidirectional"))
      (node (ref "C37") (pin "2") (pinfunction "2_2") (pintype "bidirectional"))
      (node (ref "C38") (pin "2") (pinfunction "2_2") (pintype "bidirectional"))
      (node (ref "C48") (pin "2") (pinfunction "2_2") (pintype "bidirectional"))
      (node (ref "J4") (pin "VDD") (pinfunction "VCC_VDD") (pintype "bidirectional"))
      (node (ref "R10") (pin "2") (pinfunction "2_2") (pintype "bidirectional"))
      (node (ref "R13") (pin "1") (pinfunction "1_1") (pintype "bidirectional"))
      (node (ref "R14") (pin "2") (pinfunction "2_2") (pintype "bidirectional"))
      (node (ref "R20") (pin "2") (pinfunction "2_2") (pintype "bidirectional"))
      (node (ref "R22") (pin "2") (pinfunction "2_2") (pintype "bidirectional"))
      (node (ref "U10") (pin "5") (pinfunction "VOUT_5") (pintype "bidirectional"))
      (node (ref "U12") (pin "21") (pinfunction "VDD_4_21") (pintype "bidirectional"))
      (node (ref "U12") (pin "22") (pinfunction "~{TESTEN}_22") (pintype "bidirectional"))
      (node (ref "U12") (pin "29") (pinfunction "VDD_1_29") (pintype "bidirectional"))
      (node (ref "U12") (pin "40") (pinfunction "~{SRC_INT}_40") (pintype "bidirectional"))
      (node (ref "U12") (pin "6") (pinfunction "VDD_2_6") (pintype "bidirectional"))
      (node (ref "U12") (pin "8") (pinfunction "VDD_3_8") (pintype "bidirectional"))
      (node (ref "U14") (pin "10") (pinfunction "VCC_10") (pintype "bidirectional"))
      (node (ref "U3") (pin "1") (pinfunction "A2_1") (pintype "bidirectional"))
      (node (ref "U3") (pin "18") (pinfunction "VCC_18") (pintype "bidirectional"))
      (node (ref "U3") (pin "4") (pinfunction "~{RST}_4") (pintype "bidirectional"))
      (node (ref "U4") (pin "1") (pinfunction "A2_1") (pintype "bidirectional"))
      (node (ref "U4") (pin "18") (pinfunction "VCC_18") (pintype "bidirectional"))
      (node (ref "U4") (pin "3") (pinfunction "A0_3") (pintype "bidirectional"))
      (node (ref "U4") (pin "4") (pinfunction "~{RST}_4") (pintype "bidirectional"))
      (node (ref "U5") (pin "1") (pinfunction "A2_1") (pintype "bidirectional"))
      (node (ref "U5") (pin "18") (pinfunction "VCC_18") (pintype "bidirectional"))
      (node (ref "U5") (pin "2") (pinfunction "A1_2") (pintype "bidirectional"))
      (node (ref "U5") (pin "4") (pinfunction "~{RST}_4") (pintype "bidirectional"))
      (node (ref "U6") (pin "P$19") (pinfunction "VCCB_P$19") (pintype "bidirectional"))
    )
    (net (code "2") (name "/3.8V") (class "Default")
      (node (ref "C5") (pin "1") (pinfunction "1_1") (pintype "bidirectional"))
      (node (ref "C6") (pin "1") (pinfunction "1_1") (pintype "bidirectional"))
      (node (ref "R5") (pin "1") (pinfunction "1_1") (pintype "bidirectional"))
      (node (ref "R6") (pin "1") (pinfunction "1_1") (pintype "bidirectional"))
      (node (ref "U1") (pin "P$55") (pinfunction "VBAT_P$55") (pintype "bidirectional"))
      (node (ref "U1") (pin "P$56") (pinfunction "VBAT_P$56") (pintype "bidirectional"))
      (node (ref "U1") (pin "P$57") (pinfunction "VBAT_P$57") (pintype "bidirectional"))
      (node (ref "U2") (pin "P$4") (pinfunction "VOUT_P$4") (pintype "bidirectional"))
    )
    (net (code "3") (name "/5.0V") (class "Default")
      (node (ref "C23") (pin "2") (pinfunction "2_2") (pintype "bidirectional"))
      (node (ref "C26") (pin "2") (pinfunction "2_2") (pintype "bidirectional"))
      (node (ref "C3") (pin "1") (pinfunction "1_1") (pintype "bidirectional"))
      (node (ref "C30") (pin "1") (pinfunction "1_1") (pintype "bidirectional"))
      (node (ref "C4") (pin "1") (pinfunction "1_1") (pintype "bidirectional"))
      (node (ref "C42") (pin "2") (pinfunction "2_2") (pintype "bidirectional"))
      (node (ref "C45") (pin "1") (pinfunction "1_1") (pintype "bidirectional"))
      (node (ref "C54") (pin "2") (pinfunction "2_2") (pintype "bidirectional"))
      (node (ref "J3") (pin "VIN") (pinfunction "VIN_VIN") (pintype "bidirectional"))
      (node (ref "N1") (pin "16") (pinfunction "VIN_16") (pintype "bidirectional"))
      (node (ref "U10") (pin "1") (pinfunction "VIN_1") (pintype "bidirectional"))
      (node (ref "U10") (pin "3") (pinfunction "EN_3") (pintype "bidirectional"))
      (node (ref "U11") (pin "4") (pinfunction "VOUT_4") (pintype "bidirectional"))
      (node (ref "U13") (pin "P$7") (pinfunction "VA_P$7") (pintype "bidirectional"))
      (node (ref "U15") (pin "1") (pinfunction "VIN_1") (pintype "bidirectional"))
      (node (ref "U16") (pin "5") (pinfunction "VCC_5") (pintype "bidirectional"))
      (node (ref "U2") (pin "P$2") (pinfunction "VIN_P$2") (pintype "bidirectional"))
      (node (ref "U7") (pin "5") (pinfunction "VCC_5") (pintype "bidirectional"))
    )
    (net (code "4") (name "/AMP_SHUTDOWN") (class "Default")
      (node (ref "N1") (pin "30") (pinfunction "PC7_30") (pintype "bidirectional"))
      (node (ref "R22") (pin "1") (pinfunction "1_1") (pintype "bidirectional"))
      (node (ref "U14") (pin "7") (pinfunction "SHUTDOWN_7") (pintype "bidirectional"))
    )
    (net (code "5") (name "/AMP_VOL_CLK") (class "Default")
      (node (ref "N1") (pin "29") (pinfunction "PC6_29") (pintype "bidirectional"))
      (node (ref "U14") (pin "4") (pinfunction "CLOCK_4") (pintype "bidirectional"))
    )
    (net (code "6") (name "/AMP_VOL_UPDN") (class "Default")
      (node (ref "N1") (pin "28") (pinfunction "PC5_28") (pintype "bidirectional"))
      (node (ref "U14") (pin "6") (pinfunction "UP/DN_6") (pintype "bidirectional"))
    )
    (net (code "7") (name "/AOUT_L") (class "Default")
      (node (ref "C46") (pin "1") (pinfunction "1_1") (pintype "bidirectional"))
      (node (ref "C52") (pin "1") (pinfunction "1_1") (pintype "bidirectional"))
      (node (ref "R17") (pin "2") (pinfunction "2_2") (pintype "bidirectional"))
    )
    (net (code "8") (name "/AOUT_R") (class "Default")
      (node (ref "C47") (pin "2") (pinfunction "2_2") (pintype "bidirectional"))
      (node (ref "C53") (pin "1") (pinfunction "1_1") (pintype "bidirectional"))
      (node (ref "R16") (pin "2") (pinfunction "2_2") (pintype "bidirectional"))
    )
    (net (code "9") (name "/GSM_PWR_EN") (class "Default")
      (node (ref "N1") (pin "10") (pinfunction "PA0/ADC0_10") (pintype "bidirectional"))
      (node (ref "R3") (pin "1") (pinfunction "1_1") (pintype "bidirectional"))
      (node (ref "U7") (pin "2") (pinfunction "A_2") (pintype "bidirectional"))
    )
    (net (code "10") (name "/GSM_PWR_KEY") (class "Default")
      (node (ref "N1") (pin "8") (pinfunction "PA2/ADC2_8") (pintype "bidirectional"))
      (node (ref "U6") (pin "P$13") (pinfunction "B7_P$13") (pintype "bidirectional"))
    )
    (net (code "11") (name "/GSM_RING") (class "Default")
      (node (ref "N1") (pin "9") (pinfunction "PA1/ADC1_9") (pintype "bidirectional"))
      (node (ref "U6") (pin "P$14") (pinfunction "B6_P$14") (pintype "bidirectional"))
    )
    (net (code "12") (name "/GSM_RXD") (class "Default")
      (node (ref "N1") (pin "18") (pinfunction "PD3/TXD1_18") (pintype "bidirectional"))
      (node (ref "U6") (pin "P$16") (pinfunction "B4_P$16") (pintype "bidirectional"))
    )
    (net (code "13") (name "/GSM_STATUS") (class "Default")
      (node (ref "N1") (pin "7") (pinfunction "PA3/ADC3_7") (pintype "bidirectional"))
      (node (ref "U6") (pin "P$12") (pinfunction "B8_P$12") (pintype "bidirectional"))
    )
    (net (code "14") (name "/GSM_TXD") (class "Default")
      (node (ref "N1") (pin "17") (pinfunction "PD2/RXD1_17") (pintype "bidirectional"))
      (node (ref "U6") (pin "P$15") (pinfunction "B5_P$15") (pintype "bidirectional"))
    )
    (net (code "15") (name "/I2C_SCL") (class "Default")
      (node (ref "J3") (pin "CLK") (pinfunction "CLK_CLK") (pintype "bidirectional"))
      (node (ref "N1") (pin "23") (pinfunction "PC0/SCL_23") (pintype "bidirectional"))
      (node (ref "R10") (pin "1") (pinfunction "1_1") (pintype "bidirectional"))
      (node (ref "U12") (pin "32") (pinfunction "SCL_32") (pintype "bidirectional"))
      (node (ref "U3") (pin "19") (pinfunction "SCL_19") (pintype "bidirectional"))
      (node (ref "U4") (pin "19") (pinfunction "SCL_19") (pintype "bidirectional"))
      (node (ref "U5") (pin "19") (pinfunction "SCL_19") (pintype "bidirectional"))
    )
    (net (code "16") (name "/I2C_SDA") (class "Default")
      (node (ref "J3") (pin "DATA") (pinfunction "DATA_DATA") (pintype "bidirectional"))
      (node (ref "N1") (pin "24") (pinfunction "PC1/SDA_24") (pintype "bidirectional"))
      (node (ref "R20") (pin "1") (pinfunction "1_1") (pintype "bidirectional"))
      (node (ref "U12") (pin "31") (pinfunction "SDA_31") (pintype "bidirectional"))
      (node (ref "U3") (pin "20") (pinfunction "SDA_20") (pintype "bidirectional"))
      (node (ref "U4") (pin "20") (pinfunction "SDA_20") (pintype "bidirectional"))
      (node (ref "U5") (pin "20") (pinfunction "SDA_20") (pintype "bidirectional"))
    )
    (net (code "17") (name "/MICROSD_CS") (class "Default")
      (node (ref "J4") (pin "DAT3/CS") (pinfunction "DAT3/CS_DAT3/CS") (pintype "bidirectional"))
      (node (ref "N1") (pin "6") (pinfunction "PA4/ADC4_6") (pintype "bidirectional"))
    )
    (net (code "18") (name "/SPI_MISO") (class "Default")
      (node (ref "J4") (pin "DAT0/DO") (pinfunction "DAT0/DO_DAT0/DO") (pintype "bidirectional"))
      (node (ref "N1") (pin "32") (pinfunction "MISO_32") (pintype "bidirectional"))
    )
    (net (code "19") (name "/SPI_MOSI") (class "Default")
      (node (ref "J4") (pin "CMD/DI") (pinfunction "CMD/DI_CMD/DI") (pintype "bidirectional"))
      (node (ref "N1") (pin "31") (pinfunction "MOSI_31") (pintype "bidirectional"))
      (node (ref "U12") (pin "34") (pinfunction "SDI_34") (pintype "bidirectional"))
    )
    (net (code "20") (name "/SPI_SCK") (class "Default")
      (node (ref "J4") (pin "CLK/SCK") (pinfunction "CLK/SCK_CLK/SCK") (pintype "bidirectional"))
      (node (ref "N1") (pin "33") (pinfunction "SCK_33") (pintype "bidirectional"))
      (node (ref "U12") (pin "36") (pinfunction "SCKR_36") (pintype "bidirectional"))
    )
    (net (code "21") (name "/STA013_BIT_EN") (class "Default")
      (node (ref "N1") (pin "27") (pinfunction "PC4_27") (pintype "bidirectional"))
      (node (ref "U12") (pin "38") (pinfunction "BIT_EN_38") (pintype "bidirectional"))
    )
    (net (code "22") (name "/STA013_DREQ") (class "Default")
      (node (ref "N1") (pin "26") (pinfunction "PC3_26") (pintype "bidirectional"))
      (node (ref "U12") (pin "27") (pinfunction "OUT_CLK/DATA_REC_27") (pintype "bidirectional"))
    )
    (net (code "23") (name "/STA013_LRCKT") (class "Default")
      (node (ref "U12") (pin "2") (pinfunction "LRCKT_2") (pintype "bidirectional"))
      (node (ref "U13") (pin "P$3") (pinfunction "LRCK_P$3") (pintype "bidirectional"))
    )
    (net (code "24") (name "/STA013_OCLK") (class "Default")
      (node (ref "U12") (pin "3") (pinfunction "OCLK_3") (pintype "bidirectional"))
      (node (ref "U13") (pin "P$4") (pinfunction "MCLK_P$4") (pintype "bidirectional"))
    )
    (net (code "25") (name "/STA013_SCKT") (class "Default")
      (node (ref "U12") (pin "44") (pinfunction "SCKT_44") (pintype "bidirectional"))
      (node (ref "U13") (pin "P$2") (pinfunction "DEM/SCLK_P$2") (pintype "bidirectional"))
    )
    (net (code "26") (name "/STA013_SDO") (class "Default")
      (node (ref "U12") (pin "42") (pinfunction "SDO_42") (pintype "bidirectional"))
      (node (ref "U13") (pin "P$1") (pinfunction "SDATA_P$1") (pintype "bidirectional"))
    )
    (net (code "27") (name "/VBAT") (class "Default")
      (node (ref "BAT[+-]") (pin "1") (pinfunction "1_1") (pintype "bidirectional"))
      (node (ref "S1") (pin "2") (pinfunction "1_2") (pintype "bidirectional"))
    )
    (net (code "28") (name "/VIBRATOR_EN") (class "Default")
      (node (ref "N1") (pin "14") (pinfunction "PB3_14") (pintype "bidirectional"))
      (node (ref "R23") (pin "1") (pinfunction "1_1") (pintype "bidirectional"))
      (node (ref "U16") (pin "2") (pinfunction "A_2") (pintype "bidirectional"))
    )
    (net (code "29") (name "/~{STA013_RST}") (class "Default")
      (node (ref "N1") (pin "25") (pinfunction "PC2_25") (pintype "bidirectional"))
      (node (ref "R14") (pin "1") (pinfunction "1_1") (pintype "bidirectional"))
      (node (ref "U12") (pin "25") (pinfunction "~{RESET}_25") (pintype "bidirectional"))
    )
    (net (code "30") (name "GND") (class "Default")
      (node (ref "B1") (pin "2") (pinfunction "2_2") (pintype "bidirectional"))
      (node (ref "B10") (pin "2") (pinfunction "2_2") (pintype "bidirectional"))
      (node (ref "B11") (pin "2") (pinfunction "2_2") (pintype "bidirectional"))
      (node (ref "B12") (pin "2") (pinfunction "2_2") (pintype "bidirectional"))
      (node (ref "B13") (pin "5") (pinfunction "COMMON_5") (pintype "bidirectional"))
      (node (ref "B13") (pin "GND1") (pinfunction "GND1_GND1") (pintype "bidirectional"))
      (node (ref "B13") (pin "GND2") (pinfunction "GND2_GND2") (pintype "bidirectional"))
      (node (ref "B14") (pin "1") (pinfunction "1_1") (pintype "bidirectional"))
      (node (ref "B15") (pin "2") (pinfunction "2_2") (pintype "bidirectional"))
      (node (ref "B16") (pin "1") (pinfunction "1_1") (pintype "bidirectional"))
      (node (ref "B17") (pin "2") (pinfunction "2_2") (pintype "bidirectional"))
      (node (ref "B2") (pin "2") (pinfunction "2_2") (pintype "bidirectional"))
      (node (ref "B3") (pin "2") (pinfunction "2_2") (pintype "bidirectional"))
      (node (ref "B4") (pin "2") (pinfunction "2_2") (pintype "bidirectional"))
      (node (ref "B5") (pin "2") (pinfunction "2_2") (pintype "bidirectional"))
      (node (ref "B6") (pin "2") (pinfunction "2_2") (pintype "bidirectional"))
      (node (ref "B7") (pin "2") (pinfunction "2_2") (pintype "bidirectional"))
      (node (ref "B8") (pin "2") (pinfunction "2_2") (pintype "bidirectional"))
      (node (ref "B9") (pin "2") (pinfunction "2_2") (pintype "bidirectional"))
      (node (ref "BAT[+-]") (pin "2") (pinfunction "2_2") (pintype "bidirectional"))
      (node (ref "C1") (pin "1") (pinfunction "1_1") (pintype "bidirectional"))
      (node (ref "C10") (pin "2") (pinfunction "2_2") (pintype "bidirectional"))
      (node (ref "C13") (pin "1") (pinfunction "1_1") (pintype "bidirectional"))
      (node (ref "C14") (pin "1") (pinfunction "1_1") (pintype "bidirectional"))
      (node (ref "C15") (pin "1") (pinfunction "1_1") (pintype "bidirectional"))
      (node (ref "C16") (pin "1") (pinfunction "1_1") (pintype "bidirectional"))
      (node (ref "C19") (pin "1") (pinfunction "1_1") (pintype "bidirectional"))
      (node (ref "C2") (pin "1") (pinfunction "1_1") (pintype "bidirectional"))
      (node (ref "C20") (pin "1") (pinfunction "1_1") (pintype "bidirectional"))
      (node (ref "C21") (pin "1") (pinfunction "1_1") (pintype "bidirectional"))
      (node (ref "C22") (pin "1") (pinfunction "1_1") (pintype "bidirectional"))
      (node (ref "C23") (pin "1") (pinfunction "1_1") (pintype "bidirectional"))
      (node (ref "C24") (pin "1") (pinfunction "1_1") (pintype "bidirectional"))
      (node (ref "C25") (pin "2") (pinfunction "2_2") (pintype "bidirectional"))
      (node (ref "C26") (pin "1") (pinfunction "1_1") (pintype "bidirectional"))
      (node (ref "C27") (pin "1") (pinfunction "1_1") (pintype "bidirectional"))
      (node (ref "C28") (pin "1") (pinfunction "1_1") (pintype "bidirectional"))
      (node (ref "C29") (pin "2") (pinfunction "2_2") (pintype "bidirectional"))
      (node (ref "C3") (pin "2") (pinfunction "2_2") (pintype "bidirectional"))
      (node (ref "C30") (pin "2") (pinfunction "2_2") (pintype "bidirectional"))
      (node (ref "C31") (pin "2") (pinfunction "2_2") (pintype "bidirectional"))
      (node (ref "C32") (pin "2") (pinfunction "2_2") (pintype "bidirectional"))
      (node (ref "C33") (pin "1") (pinfunction "1_1") (pintype "bidirectional"))
      (node (ref "C34") (pin "1") (pinfunction "1_1") (pintype "bidirectional"))
      (node (ref "C35") (pin "1") (pinfunction "1_1") (pintype "bidirectional"))
      (node (ref "C36") (pin "1") (pinfunction "1_1") (pintype "bidirectional"))
      (node (ref "C37") (pin "1") (pinfunction "1_1") (pintype "bidirectional"))
      (node (ref "C38") (pin "1") (pinfunction "1_1") (pintype "bidirectional"))
      (node (ref "C4") (pin "2") (pinfunction "2_2") (pintype "bidirectional"))
      (node (ref "C40") (pin "1") (pinfunction "1_1") (pintype "bidirectional"))
      (node (ref "C41") (pin "1") (pinfunction "1_1") (pintype "bidirectional"))
      (node (ref "C42") (pin "1") (pinfunction "1_1") (pintype "bidirectional"))
      (node (ref "C45") (pin "2") (pinfunction "2_2") (pintype "bidirectional"))
      (node (ref "C46") (pin "2") (pinfunction "2_2") (pintype "bidirectional"))
      (node (ref "C47") (pin "1") (pinfunction "1_1") (pintype "bidirectional"))
      (node (ref "C48") (pin "1") (pinfunction "1_1") (pintype "bidirectional"))
      (node (ref "C5") (pin "2") (pinfunction "2_2") (pintype "bidirectional"))
      (node (ref "C51") (pin "1") (pinfunction "1_1") (pintype "bidirectional"))
      (node (ref "C54") (pin "1") (pinfunction "1_1") (pintype "bidirectional"))
      (node (ref "C55") (pin "1") (pinfunction "1_1") (pintype "bidirectional"))
      (node (ref "C6") (pin "2") (pinfunction "2_2") (pintype "bidirectional"))
      (node (ref "C7") (pin "1") (pinfunction "1_1") (pintype "bidirectional"))
      (node (ref "C8") (pin "1") (pinfunction "1_1") (pintype "bidirectional"))
      (node (ref "C9") (pin "1") (pinfunction "1_1") (pintype "bidirectional"))
      (node (ref "J3") (pin "GND") (pinfunction "GND_GND") (pintype "bidirectional"))
      (node (ref "J4") (pin "GND1") (pinfunction "GND_1_GND1") (pintype "bidirectional"))
      (node (ref "J4") (pin "GND2") (pinfunction "GND_2_GND2") (pintype "bidirectional"))
      (node (ref "J4") (pin "GND3") (pinfunction "GND_3_GND3") (pintype "bidirectional"))
      (node (ref "J4") (pin "GND4") (pinfunction "GND_4_GND4") (pintype "bidirectional"))
      (node (ref "J4") (pin "VSS") (pinfunction "GND_VSS") (pintype "bidirectional"))
      (node (ref "J5") (pin "1") (pinfunction "SLEEVE_1") (pintype "bidirectional"))
      (node (ref "J6") (pin "P$1") (pinfunction "GND_P$1") (pintype "bidirectional"))
      (node (ref "J6") (pin "P$2") (pinfunction "GND_P$2") (pintype "bidirectional"))
      (node (ref "M1") (pin "1") (pinfunction "-_1") (pintype "bidirectional"))
      (node (ref "N1") (pin "1") (pinfunction "GND_1") (pintype "bidirectional"))
      (node (ref "N1") (pin "15") (pinfunction "GND_15") (pintype "bidirectional"))
      (node (ref "N1") (pin "35") (pinfunction "GND_35") (pintype "bidirectional"))
      (node (ref "R1") (pin "1") (pinfunction "1_1") (pintype "bidirectional"))
      (node (ref "R12") (pin "2") (pinfunction "2_2") (pintype "bidirectional"))
      (node (ref "R18") (pin "2") (pinfunction "2_2") (pintype "bidirectional"))
      (node (ref "R19") (pin "1") (pinfunction "1_1") (pintype "bidirectional"))
      (node (ref "R2") (pin "1") (pinfunction "1_1") (pintype "bidirectional"))
      (node (ref "R23") (pin "2") (pinfunction "2_2") (pintype "bidirectional"))
      (node (ref "R3") (pin "2") (pinfunction "2_2") (pintype "bidirectional"))
      (node (ref "R4") (pin "2") (pinfunction "2_2") (pintype "bidirectional"))
      (node (ref "R6") (pin "2") (pinfunction "2_2") (pintype "bidirectional"))
      (node (ref "U1") (pin "P$17") (pinfunction "GND_P$17") (pintype "bidirectional"))
      (node (ref "U1") (pin "P$18") (pinfunction "GND_P$18") (pintype "bidirectional"))
      (node (ref "U1") (pin "P$2") (pinfunction "GND_P$2") (pintype "bidirectional"))
      (node (ref "U1") (pin "P$29") (pinfunction "GND_P$29") (pintype "bidirectional"))
      (node (ref "U1") (pin "P$39") (pinfunction "GND_P$39") (pintype "bidirectional"))
      (node (ref "U1") (pin "P$45") (pinfunction "GND_P$45") (pintype "bidirectional"))
      (node (ref "U1") (pin "P$46") (pinfunction "GND_P$46") (pintype "bidirectional"))
      (node (ref "U1") (pin "P$54") (pinfunction "GND_P$54") (pintype "bidirectional"))
      (node (ref "U1") (pin "P$58") (pinfunction "GND_P$58") (pintype "bidirectional"))
      (node (ref "U1") (pin "P$59") (pinfunction "GND_P$59") (pintype "bidirectional"))
      (node (ref "U1") (pin "P$61") (pinfunction "GND_P$61") (pintype "bidirectional"))
      (node (ref "U1") (pin "P$62") (pinfunction "GND_P$62") (pintype "bidirectional"))
      (node (ref "U1") (pin "P$63") (pinfunction "GND_P$63") (pintype "bidirectional"))
      (node (ref "U1") (pin "P$64") (pinfunction "GND_P$64") (pintype "bidirectional"))
      (node (ref "U1") (pin "P$65") (pinfunction "GND_P$65") (pintype "bidirectional"))
      (node (ref "U10") (pin "2") (pinfunction "GND_2") (pintype "bidirectional"))
      (node (ref "U11") (pin "6") (pinfunction "PGND_6") (pintype "bidirectional"))
      (node (ref "U11") (pin "7") (pinfunction "SGND_7") (pintype "bidirectional"))
      (node (ref "U12") (pin "19") (pinfunction "VSS_4_19") (pintype "bidirectional"))
      (node (ref "U12") (pin "24") (pinfunction "SCANEN_24") (pintype "bidirectional"))
      (node (ref "U12") (pin "26") (pinfunction "VSS_5_26") (pintype "bidirectional"))
      (node (ref "U12") (pin "30") (pinfunction "VSS_1_30") (pintype "bidirectional"))
      (node (ref "U12") (pin "5") (pinfunction "VSS_2_5") (pintype "bidirectional"))
      (node (ref "U12") (pin "7") (pinfunction "VSS_3_7") (pintype "bidirectional"))
      (node (ref "U13") (pin "P$6") (pinfunction "AGND_P$6") (pintype "bidirectional"))
      (node (ref "U14") (pin "5") (pinfunction "GND_5") (pintype "bidirectional"))
      (node (ref "U15") (pin "2") (pinfunction "GND_2") (pintype "bidirectional"))
      (node (ref "U16") (pin "1") (pinfunction "~{OE}_1") (pintype "bidirectional"))
      (node (ref "U16") (pin "3") (pinfunction "GND_3") (pintype "bidirectional"))
      (node (ref "U2") (pin "P$3") (pinfunction "GND_P$3") (pintype "bidirectional"))
      (node (ref "U2") (pin "P$6") (pinfunction "GND_P$6") (pintype "bidirectional"))
      (node (ref "U3") (pin "17") (pinfunction "GND_17") (pintype "bidirectional"))
      (node (ref "U3") (pin "2") (pinfunction "A1_2") (pintype "bidirectional"))
      (node (ref "U3") (pin "3") (pinfunction "A0_3") (pintype "bidirectional"))
      (node (ref "U3") (pin "PAD") (pinfunction "PAD_PAD") (pintype "bidirectional"))
      (node (ref "U4") (pin "17") (pinfunction "GND_17") (pintype "bidirectional"))
      (node (ref "U4") (pin "2") (pinfunction "A1_2") (pintype "bidirectional"))
      (node (ref "U4") (pin "PAD") (pinfunction "PAD_PAD") (pintype "bidirectional"))
      (node (ref "U5") (pin "17") (pinfunction "GND_17") (pintype "bidirectional"))
      (node (ref "U5") (pin "3") (pinfunction "A0_3") (pintype "bidirectional"))
      (node (ref "U5") (pin "PAD") (pinfunction "PAD_PAD") (pintype "bidirectional"))
      (node (ref "U6") (pin "P$11") (pinfunction "GND_P$11") (pintype "bidirectional"))
      (node (ref "U7") (pin "1") (pinfunction "~{OE}_1") (pintype "bidirectional"))
      (node (ref "U7") (pin "3") (pinfunction "GND_3") (pintype "bidirectional"))
      (node (ref "U8") (pin "C5") (pinfunction "GND_C5") (pintype "bidirectional"))
      (node (ref "U8") (pin "GND@L") (pinfunction "GND_GND@L") (pintype "bidirectional"))
      (node (ref "U8") (pin "GND@R") (pinfunction "GND_GND@R") (pintype "bidirectional"))
      (node (ref "U9") (pin "P$2") (pinfunction "COMMON_P$2") (pintype "bidirectional"))
      (node (ref "X2") (pin "2") (pinfunction "GND0_2") (pintype "bidirectional"))
      (node (ref "X2") (pin "4") (pinfunction "GND1_4") (pintype "bidirectional"))
    )
    (net (code "31") (name "Net-(B13-A)") (class "Default")
      (node (ref "B13") (pin "1") (pinfunction "A_1") (pintype "bidirectional"))
      (node (ref "U3") (pin "11") (pinfunction "GP2_11") (pintype "bidirectional"))
    )
    (net (code "32") (name "Net-(B13-B)") (class "Default")
      (node (ref "B13") (pin "4") (pinfunction "B_4") (pintype "bidirectional"))
      (node (ref "U3") (pin "9") (pinfunction "GP0_9") (pintype "bidirectional"))
    )
    (net (code "33") (name "Net-(B13-C)") (class "Default")
      (node (ref "B13") (pin "3") (pinfunction "C_3") (pintype "bidirectional"))
      (node (ref "U3") (pin "13") (pinfunction "GP4_13") (pintype "bidirectional"))
    )
    (net (code "34") (name "Net-(B13-CENTER)") (class "Default")
      (node (ref "B13") (pin "2") (pinfunction "CENTER_2") (pintype "bidirectional"))
      (node (ref "U3") (pin "12") (pinfunction "GP3_12") (pintype "bidirectional"))
    )
    (net (code "35") (name "Net-(B13-D)") (class "Default")
      (node (ref "B13") (pin "6") (pinfunction "D_6") (pintype "bidirectional"))
      (node (ref "U3") (pin "10") (pinfunction "GP1_10") (pintype "bidirectional"))
    )
    (net (code "36") (name "Net-(C41-Pad2)") (class "Default")
      (node (ref "C41") (pin "2") (pinfunction "2_2") (pintype "bidirectional"))
      (node (ref "R15") (pin "2") (pinfunction "2_2") (pintype "bidirectional"))
    )
    (net (code "37") (name "Net-(C43-Pad1)") (class "Default")
      (node (ref "C43") (pin "1") (pinfunction "1_1") (pintype "bidirectional"))
      (node (ref "R17") (pin "1") (pinfunction "1_1") (pintype "bidirectional"))
    )
    (net (code "38") (name "Net-(C44-Pad1)") (class "Default")
      (node (ref "C44") (pin "1") (pinfunction "1_1") (pintype "bidirectional"))
      (node (ref "R16") (pin "1") (pinfunction "1_1") (pintype "bidirectional"))
    )
    (net (code "39") (name "Net-(J5-RING)") (class "Default")
      (node (ref "C50") (pin "1") (pinfunction "1_1") (pintype "bidirectional"))
      (node (ref "J5") (pin "3") (pinfunction "RING_3") (pintype "bidirectional"))
    )
    (net (code "40") (name "Net-(J5-TIP)") (class "Default")
      (node (ref "C49") (pin "1") (pinfunction "1_1") (pintype "bidirectional"))
      (node (ref "J5") (pin "2") (pinfunction "TIP_2") (pintype "bidirectional"))
    )
    (net (code "41") (name "Net-(J6-SIG)") (class "Default")
      (node (ref "J6") (pin "P$3") (pinfunction "SIG_P$3") (pintype "bidirectional"))
      (node (ref "U1") (pin "P$60") (pinfunction "RF_ANT_P$60") (pintype "bidirectional"))
    )
    (net (code "42") (name "Net-(M1-+)") (class "Default")
      (node (ref "C55") (pin "2") (pinfunction "2_2") (pintype "bidirectional"))
      (node (ref "M1") (pin "2") (pinfunction "+_2") (pintype "bidirectional"))
      (node (ref "U15") (pin "5") (pinfunction "VOUT_5") (pintype "bidirectional"))
    )
    (net (code "43") (name "Net-(S1-2)") (class "Default")
      (node (ref "C25") (pin "1") (pinfunction "1_1") (pintype "bidirectional"))
      (node (ref "L1") (pin "1") (pinfunction "1_1") (pintype "bidirectional"))
      (node (ref "S1") (pin "3") (pinfunction "2_3") (pintype "bidirectional"))
      (node (ref "U11") (pin "1") (pinfunction "EN_1") (pintype "bidirectional"))
      (node (ref "U11") (pin "8") (pinfunction "VIN_8") (pintype "bidirectional"))
    )
    (net (code "44") (name "Net-(U1-MIC_N)") (class "Default")
      (node (ref "C17") (pin "1") (pinfunction "1_1") (pintype "bidirectional"))
      (node (ref "C18") (pin "1") (pinfunction "1_1") (pintype "bidirectional"))
      (node (ref "C19") (pin "2") (pinfunction "2_2") (pintype "bidirectional"))
      (node (ref "C22") (pin "2") (pinfunction "2_2") (pintype "bidirectional"))
      (node (ref "J2") (pin "-") (pinfunction "-_-") (pintype "bidirectional"))
      (node (ref "U1") (pin "P$20") (pinfunction "MIC_N_P$20") (pintype "bidirectional"))
    )
    (net (code "45") (name "Net-(U1-MIC_P)") (class "Default")
      (node (ref "C17") (pin "2") (pinfunction "2_2") (pintype "bidirectional"))
      (node (ref "C18") (pin "2") (pinfunction "2_2") (pintype "bidirectional"))
      (node (ref "C20") (pin "2") (pinfunction "2_2") (pintype "bidirectional"))
      (node (ref "C21") (pin "2") (pinfunction "2_2") (pintype "bidirectional"))
      (node (ref "J2") (pin "+") (pinfunction "+_+") (pintype "bidirectional"))
      (node (ref "U1") (pin "P$19") (pinfunction "MIC_P_P$19") (pintype "bidirectional"))
    )
    (net (code "46") (name "Net-(U1-PWRKEY)") (class "Default")
      (node (ref "U1") (pin "P$1") (pinfunction "PWRKEY_P$1") (pintype "bidirectional"))
      (node (ref "U6") (pin "P$8") (pinfunction "A7_P$8") (pintype "bidirectional"))
    )
    (net (code "47") (name "Net-(U1-RI)") (class "Default")
      (node (ref "U1") (pin "P$4") (pinfunction "RI_P$4") (pintype "bidirectional"))
      (node (ref "U6") (pin "P$7") (pinfunction "A6_P$7") (pintype "bidirectional"))
    )
    (net (code "48") (name "Net-(U1-RXD)") (class "Default")
      (node (ref "U1") (pin "P$10") (pinfunction "RXD_P$10") (pintype "bidirectional"))
      (node (ref "U6") (pin "P$5") (pinfunction "A4_P$5") (pintype "bidirectional"))
    )
    (net (code "49") (name "Net-(U1-SPK_N)") (class "Default")
      (node (ref "C11") (pin "2") (pinfunction "2_2") (pintype "bidirectional"))
      (node (ref "C12") (pin "2") (pinfunction "2_2") (pintype "bidirectional"))
      (node (ref "C14") (pin "2") (pinfunction "2_2") (pintype "bidirectional"))
      (node (ref "C15") (pin "2") (pinfunction "2_2") (pintype "bidirectional"))
      (node (ref "J1") (pin "-") (pinfunction "-_-") (pintype "bidirectional"))
      (node (ref "U1") (pin "P$22") (pinfunction "SPK_N_P$22") (pintype "bidirectional"))
    )
    (net (code "50") (name "Net-(U1-SPK_P)") (class "Default")
      (node (ref "C11") (pin "1") (pinfunction "1_1") (pintype "bidirectional"))
      (node (ref "C12") (pin "1") (pinfunction "1_1") (pintype "bidirectional"))
      (node (ref "C13") (pin "2") (pinfunction "2_2") (pintype "bidirectional"))
      (node (ref "C16") (pin "2") (pinfunction "2_2") (pintype "bidirectional"))
      (node (ref "J1") (pin "+") (pinfunction "+_+") (pintype "bidirectional"))
      (node (ref "U1") (pin "P$21") (pinfunction "SPK_P_P$21") (pintype "bidirectional"))
    )
    (net (code "51") (name "Net-(U1-STATUS)") (class "Default")
      (node (ref "U1") (pin "P$66") (pinfunction "STATUS_P$66") (pintype "bidirectional"))
      (node (ref "U6") (pin "P$9") (pinfunction "A8_P$9") (pintype "bidirectional"))
    )
    (net (code "52") (name "Net-(U1-TXD)") (class "Default")
      (node (ref "U1") (pin "P$9") (pinfunction "TXD_P$9") (pintype "bidirectional"))
      (node (ref "U6") (pin "P$6") (pinfunction "A5_P$6") (pintype "bidirectional"))
    )
    (net (code "53") (name "Net-(U1-USIM_CLK)") (class "Default")
      (node (ref "C8") (pin "2") (pinfunction "2_2") (pintype "bidirectional"))
      (node (ref "R8") (pin "2") (pinfunction "2_2") (pintype "bidirectional"))
      (node (ref "U1") (pin "P$32") (pinfunction "USIM_CLK_P$32") (pintype "bidirectional"))
    )
    (net (code "54") (name "Net-(U1-USIM_DATA)") (class "Default")
      (node (ref "C7") (pin "2") (pinfunction "2_2") (pintype "bidirectional"))
      (node (ref "R9") (pin "2") (pinfunction "2_2") (pintype "bidirectional"))
      (node (ref "U1") (pin "P$31") (pinfunction "USIM_DATA_P$31") (pintype "bidirectional"))
    )
    (net (code "55") (name "Net-(U1-USIM_RST)") (class "Default")
      (node (ref "C9") (pin "2") (pinfunction "2_2") (pintype "bidirectional"))
      (node (ref "R7") (pin "2") (pinfunction "2_2") (pintype "bidirectional"))
      (node (ref "U1") (pin "P$33") (pinfunction "USIM_RST_P$33") (pintype "bidirectional"))
    )
    (net (code "56") (name "Net-(U1-USIM_VDD)") (class "Default")
      (node (ref "C10") (pin "1") (pinfunction "1_1") (pintype "bidirectional"))
      (node (ref "U1") (pin "P$30") (pinfunction "USIM_VDD_P$30") (pintype "bidirectional"))
      (node (ref "U8") (pin "C1") (pinfunction "VCC_C1") (pintype "bidirectional"))
      (node (ref "U9") (pin "P$6") (pinfunction "X5_P$6") (pintype "bidirectional"))
    )
    (net (code "57") (name "Net-(U1-VDD_EXT)") (class "Default")
      (node (ref "C1") (pin "2") (pinfunction "2_2") (pintype "bidirectional"))
      (node (ref "U1") (pin "P$15") (pinfunction "VDD_EXT_P$15") (pintype "bidirectional"))
      (node (ref "U6") (pin "P$10") (pinfunction "OE_P$10") (pintype "bidirectional"))
      (node (ref "U6") (pin "P$2") (pinfunction "VCCA_P$2") (pintype "bidirectional"))
    )
    (net (code "58") (name "Net-(U2-ADJ)") (class "Default")
      (node (ref "R4") (pin "1") (pinfunction "1_1") (pintype "bidirectional"))
      (node (ref "R5") (pin "2") (pinfunction "2_2") (pintype "bidirectional"))
      (node (ref "U2") (pin "P$5") (pinfunction "ADJ_P$5") (pintype "bidirectional"))
    )
    (net (code "59") (name "Net-(U2-EN)") (class "Default")
      (node (ref "U2") (pin "P$1") (pinfunction "EN_P$1") (pintype "bidirectional"))
      (node (ref "U7") (pin "4") (pinfunction "Y_4") (pintype "bidirectional"))
    )
    (net (code "60") (name "Net-(U3-GP5)") (class "Default")
      (node (ref "B14") (pin "2") (pinfunction "2_2") (pintype "bidirectional"))
      (node (ref "U3") (pin "14") (pinfunction "GP5_14") (pintype "bidirectional"))
    )
    (net (code "61") (name "Net-(U3-GP6)") (class "Default")
      (node (ref "B16") (pin "2") (pinfunction "2_2") (pintype "bidirectional"))
      (node (ref "U3") (pin "15") (pinfunction "GP6_15") (pintype "bidirectional"))
    )
    (net (code "62") (name "Net-(U3-GP7)") (class "Default")
      (node (ref "B17") (pin "1") (pinfunction "1_1") (pintype "bidirectional"))
      (node (ref "U3") (pin "16") (pinfunction "GP7_16") (pintype "bidirectional"))
    )
    (net (code "63") (name "Net-(U4-GP0)") (class "Default")
      (node (ref "B15") (pin "1") (pinfunction "1_1") (pintype "bidirectional"))
      (node (ref "U4") (pin "9") (pinfunction "GP0_9") (pintype "bidirectional"))
    )
    (net (code "64") (name "Net-(U4-GP1)") (class "Default")
      (node (ref "B9") (pin "1") (pinfunction "1_1") (pintype "bidirectional"))
      (node (ref "U4") (pin "10") (pinfunction "GP1_10") (pintype "bidirectional"))
    )
    (net (code "65") (name "Net-(U4-GP2)") (class "Default")
      (node (ref "B5") (pin "1") (pinfunction "1_1") (pintype "bidirectional"))
      (node (ref "U4") (pin "11") (pinfunction "GP2_11") (pintype "bidirectional"))
    )
    (net (code "66") (name "Net-(U4-GP3)") (class "Default")
      (node (ref "B1") (pin "1") (pinfunction "1_1") (pintype "bidirectional"))
      (node (ref "U4") (pin "12") (pinfunction "GP3_12") (pintype "bidirectional"))
    )
    (net (code "67") (name "Net-(U4-GP4)") (class "Default")
      (node (ref "B10") (pin "1") (pinfunction "1_1") (pintype "bidirectional"))
      (node (ref "U4") (pin "13") (pinfunction "GP4_13") (pintype "bidirectional"))
    )
    (net (code "68") (name "Net-(U4-GP5)") (class "Default")
      (node (ref "B6") (pin "1") (pinfunction "1_1") (pintype "bidirectional"))
      (node (ref "U4") (pin "14") (pinfunction "GP5_14") (pintype "bidirectional"))
    )
    (net (code "69") (name "Net-(U4-GP6)") (class "Default")
      (node (ref "B2") (pin "1") (pinfunction "1_1") (pintype "bidirectional"))
      (node (ref "U4") (pin "15") (pinfunction "GP6_15") (pintype "bidirectional"))
    )
    (net (code "70") (name "Net-(U4-GP7)") (class "Default")
      (node (ref "B11") (pin "1") (pinfunction "1_1") (pintype "bidirectional"))
      (node (ref "U4") (pin "16") (pinfunction "GP7_16") (pintype "bidirectional"))
    )
    (net (code "71") (name "Net-(U5-GP0)") (class "Default")
      (node (ref "B3") (pin "1") (pinfunction "1_1") (pintype "bidirectional"))
      (node (ref "U5") (pin "9") (pinfunction "GP0_9") (pintype "bidirectional"))
    )
    (net (code "72") (name "Net-(U5-GP1)") (class "Default")
      (node (ref "B4") (pin "1") (pinfunction "1_1") (pintype "bidirectional"))
      (node (ref "U5") (pin "10") (pinfunction "GP1_10") (pintype "bidirectional"))
    )
    (net (code "73") (name "Net-(U5-GP2)") (class "Default")
      (node (ref "B7") (pin "1") (pinfunction "1_1") (pintype "bidirectional"))
      (node (ref "U5") (pin "11") (pinfunction "GP2_11") (pintype "bidirectional"))
    )
    (net (code "74") (name "Net-(U5-GP3)") (class "Default")
      (node (ref "B8") (pin "1") (pinfunction "1_1") (pintype "bidirectional"))
      (node (ref "U5") (pin "12") (pinfunction "GP3_12") (pintype "bidirectional"))
    )
    (net (code "75") (name "Net-(U5-GP4)") (class "Default")
      (node (ref "B12") (pin "1") (pinfunction "1_1") (pintype "bidirectional"))
      (node (ref "U5") (pin "13") (pinfunction "GP4_13") (pintype "bidirectional"))
    )
    (net (code "76") (name "Net-(U6-A1)") (class "Default")
      (node (ref "R2") (pin "2") (pinfunction "2_2") (pintype "bidirectional"))
      (node (ref "U6") (pin "P$1") (pinfunction "A1_P$1") (pintype "bidirectional"))
      (node (ref "U6") (pin "P$3") (pinfunction "A2_P$3") (pintype "bidirectional"))
      (node (ref "U6") (pin "P$4") (pinfunction "A3_P$4") (pintype "bidirectional"))
    )
    (net (code "77") (name "Net-(U6-B1)") (class "Default")
      (node (ref "R1") (pin "2") (pinfunction "2_2") (pintype "bidirectional"))
      (node (ref "U6") (pin "P$17") (pinfunction "B3_P$17") (pintype "bidirectional"))
      (node (ref "U6") (pin "P$18") (pinfunction "B2_P$18") (pintype "bidirectional"))
      (node (ref "U6") (pin "P$20") (pinfunction "B1_P$20") (pintype "bidirectional"))
    )
    (net (code "78") (name "Net-(U8-CLK)") (class "Default")
      (node (ref "R8") (pin "1") (pinfunction "1_1") (pintype "bidirectional"))
      (node (ref "U8") (pin "C3") (pinfunction "CLK_C3") (pintype "bidirectional"))
      (node (ref "U9") (pin "P$4") (pinfunction "X3_P$4") (pintype "bidirectional"))
    )
    (net (code "79") (name "Net-(U8-IO)") (class "Default")
      (node (ref "R9") (pin "1") (pinfunction "1_1") (pintype "bidirectional"))
      (node (ref "U8") (pin "C7") (pinfunction "IO_C7") (pintype "bidirectional"))
      (node (ref "U9") (pin "P$5") (pinfunction "X4_P$5") (pintype "bidirectional"))
    )
    (net (code "80") (name "Net-(U8-RST)") (class "Default")
      (node (ref "R7") (pin "1") (pinfunction "1_1") (pintype "bidirectional"))
      (node (ref "U8") (pin "C2") (pinfunction "RST_C2") (pintype "bidirectional"))
      (node (ref "U9") (pin "P$3") (pinfunction "X2_P$3") (pintype "bidirectional"))
    )
    (net (code "81") (name "Net-(U11-SW)") (class "Default")
      (node (ref "L1") (pin "2") (pinfunction "2_2") (pintype "bidirectional"))
      (node (ref "U11") (pin "5") (pinfunction "SW_5") (pintype "bidirectional"))
    )
    (net (code "82") (name "Net-(U12-FILT)") (class "Default")
      (node (ref "C40") (pin "2") (pinfunction "2_2") (pintype "bidirectional"))
      (node (ref "R15") (pin "1") (pinfunction "1_1") (pintype "bidirectional"))
      (node (ref "U12") (pin "12") (pinfunction "FILT_12") (pintype "bidirectional"))
    )
    (net (code "83") (name "Net-(U12-PVDD)") (class "Default")
      (node (ref "C39") (pin "1") (pinfunction "1_1") (pintype "bidirectional"))
      (node (ref "R13") (pin "2") (pinfunction "2_2") (pintype "bidirectional"))
      (node (ref "U12") (pin "10") (pinfunction "PVDD_10") (pintype "bidirectional"))
    )
    (net (code "84") (name "Net-(U12-PVSS)") (class "Default")
      (node (ref "C39") (pin "2") (pinfunction "2_2") (pintype "bidirectional"))
      (node (ref "R12") (pin "1") (pinfunction "1_1") (pintype "bidirectional"))
      (node (ref "U12") (pin "11") (pinfunction "PVSS_11") (pintype "bidirectional"))
    )
    (net (code "85") (name "Net-(U12-XTI)") (class "Default")
      (node (ref "C34") (pin "2") (pinfunction "2_2") (pintype "bidirectional"))
      (node (ref "R11") (pin "1") (pinfunction "1_1") (pintype "bidirectional"))
      (node (ref "U12") (pin "15") (pinfunction "XTI_15") (pintype "bidirectional"))
      (node (ref "X2") (pin "1") (pinfunction "1_1") (pintype "bidirectional"))
    )
    (net (code "86") (name "Net-(U12-XTO)") (class "Default")
      (node (ref "C33") (pin "2") (pinfunction "2_2") (pintype "bidirectional"))
      (node (ref "R11") (pin "2") (pinfunction "2_2") (pintype "bidirectional"))
      (node (ref "U12") (pin "13") (pinfunction "XTO_13") (pintype "bidirectional"))
      (node (ref "X2") (pin "3") (pinfunction "2_3") (pintype "bidirectional"))
    )
    (net (code "87") (name "Net-(U13-AOUTL)") (class "Default")
      (node (ref "C43") (pin "2") (pinfunction "2_2") (pintype "bidirectional"))
      (node (ref "R18") (pin "1") (pinfunction "1_1") (pintype "bidirectional"))
      (node (ref "U13") (pin "P$8") (pinfunction "AOUTL_P$8") (pintype "bidirectional"))
    )
    (net (code "88") (name "Net-(U13-AOUTR)") (class "Default")
      (node (ref "C44") (pin "2") (pinfunction "2_2") (pintype "bidirectional"))
      (node (ref "R19") (pin "2") (pinfunction "2_2") (pintype "bidirectional"))
      (node (ref "U13") (pin "P$5") (pinfunction "AOUTR_P$5") (pintype "bidirectional"))
    )
    (net (code "89") (name "Net-(U14-BYPASS)") (class "Default")
      (node (ref "C51") (pin "2") (pinfunction "2_2") (pintype "bidirectional"))
      (node (ref "U14") (pin "3") (pinfunction "BYPASS_3") (pintype "bidirectional"))
    )
    (net (code "90") (name "Net-(U14-VIN1)") (class "Default")
      (node (ref "C52") (pin "2") (pinfunction "2_2") (pintype "bidirectional"))
      (node (ref "U14") (pin "2") (pinfunction "VIN1_2") (pintype "bidirectional"))
    )
    (net (code "91") (name "Net-(U14-VIN2)") (class "Default")
      (node (ref "C53") (pin "2") (pinfunction "2_2") (pintype "bidirectional"))
      (node (ref "U14") (pin "8") (pinfunction "VIN2_8") (pintype "bidirectional"))
    )
    (net (code "92") (name "Net-(U14-VOUT1)") (class "Default")
      (node (ref "C49") (pin "2") (pinfunction "2_2") (pintype "bidirectional"))
      (node (ref "U14") (pin "1") (pinfunction "VOUT1_1") (pintype "bidirectional"))
    )
    (net (code "93") (name "Net-(U14-VOUT2)") (class "Default")
      (node (ref "C50") (pin "2") (pinfunction "2_2") (pintype "bidirectional"))
      (node (ref "U14") (pin "9") (pinfunction "VOUT2_9") (pintype "bidirectional"))
    )
    (net (code "94") (name "Net-(U15-EN)") (class "Default")
      (node (ref "U15") (pin "3") (pinfunction "EN_3") (pintype "bidirectional"))
      (node (ref "U16") (pin "4") (pinfunction "Y_4") (pintype "bidirectional"))
    )
    (net (code "95") (name "unconnected-(J3-Pad3V3)") (class "Default")
      (node (ref "J3") (pin "3V3") (pinfunction "3V3_3V3") (pintype "bidirectional"))
    )
    (net (code "96") (name "unconnected-(J3-PadCS)") (class "Default")
      (node (ref "J3") (pin "CS") (pinfunction "CS_CS") (pintype "bidirectional"))
    )
    (net (code "97") (name "unconnected-(J3-PadDC)") (class "Default")
      (node (ref "J3") (pin "DC") (pinfunction "DC_DC") (pintype "bidirectional"))
    )
    (net (code "98") (name "unconnected-(J3-PadRST)") (class "Default")
      (node (ref "J3") (pin "RST") (pinfunction "RST_RST") (pintype "bidirectional"))
    )
    (net (code "99") (name "unconnected-(J4-DET_A-PadSW_A)") (class "Default")
      (node (ref "J4") (pin "SW_A") (pinfunction "DET_A_SW_A") (pintype "bidirectional"))
    )
    (net (code "100") (name "unconnected-(J4-DET_B-PadSW_B)") (class "Default")
      (node (ref "J4") (pin "SW_B") (pinfunction "DET_B_SW_B") (pintype "bidirectional"))
    )
    (net (code "101") (name "unconnected-(J4-PadDAT1)") (class "Default")
      (node (ref "J4") (pin "DAT1") (pinfunction "DAT1_DAT1") (pintype "bidirectional"))
    )
    (net (code "102") (name "unconnected-(J4-PadDAT2)") (class "Default")
      (node (ref "J4") (pin "DAT2") (pinfunction "DAT2_DAT2") (pintype "bidirectional"))
    )
    (net (code "103") (name "unconnected-(N1-PA5{slash}ADC5-Pad5)") (class "Default")
      (node (ref "N1") (pin "5") (pinfunction "PA5/ADC5_5") (pintype "bidirectional"))
    )
    (net (code "104") (name "unconnected-(N1-PA6{slash}ADC6-Pad4)") (class "Default")
      (node (ref "N1") (pin "4") (pinfunction "PA6/ADC6_4") (pintype "bidirectional"))
    )
    (net (code "105") (name "unconnected-(N1-PA7{slash}ADC7-Pad3)") (class "Default")
      (node (ref "N1") (pin "3") (pinfunction "PA7/ADC7_3") (pintype "bidirectional"))
    )
    (net (code "106") (name "unconnected-(N1-PB0-Pad11)") (class "Default")
      (node (ref "N1") (pin "11") (pinfunction "PB0_11") (pintype "bidirectional"))
    )
    (net (code "107") (name "unconnected-(N1-PB1-Pad12)") (class "Default")
      (node (ref "N1") (pin "12") (pinfunction "PB1_12") (pintype "bidirectional"))
    )
    (net (code "108") (name "unconnected-(N1-PB2-Pad13)") (class "Default")
      (node (ref "N1") (pin "13") (pinfunction "PB2_13") (pintype "bidirectional"))
    )
    (net (code "109") (name "unconnected-(N1-PD4-Pad19)") (class "Default")
      (node (ref "N1") (pin "19") (pinfunction "PD4_19") (pintype "bidirectional"))
    )
    (net (code "110") (name "unconnected-(N1-PD5-Pad20)") (class "Default")
      (node (ref "N1") (pin "20") (pinfunction "PD5_20") (pintype "bidirectional"))
    )
    (net (code "111") (name "unconnected-(N1-PD6-Pad21)") (class "Default")
      (node (ref "N1") (pin "21") (pinfunction "PD6_21") (pintype "bidirectional"))
    )
    (net (code "112") (name "unconnected-(N1-PD7-Pad22)") (class "Default")
      (node (ref "N1") (pin "22") (pinfunction "PD7_22") (pintype "bidirectional"))
    )
    (net (code "113") (name "unconnected-(N1-VUSB-Pad2)") (class "Default")
      (node (ref "N1") (pin "2") (pinfunction "VUSB_2") (pintype "bidirectional"))
    )
    (net (code "114") (name "unconnected-(N1-~{RST}-Pad34)") (class "Default")
      (node (ref "N1") (pin "34") (pinfunction "~{RST}_34") (pintype "bidirectional"))
    )
    (net (code "115") (name "unconnected-(S1-3-Pad1)") (class "Default")
      (node (ref "S1") (pin "1") (pinfunction "3_1") (pintype "bidirectional"))
    )
    (net (code "116") (name "unconnected-(U1-ADC-PadP$25)") (class "Default")
      (node (ref "U1") (pin "P$25") (pinfunction "ADC_P$25") (pintype "bidirectional"))
    )
    (net (code "117") (name "unconnected-(U1-CTS-PadP$7)") (class "Default")
      (node (ref "U1") (pin "P$7") (pinfunction "CTS_P$7") (pintype "bidirectional"))
    )
    (net (code "118") (name "unconnected-(U1-DCD-PadP$5)") (class "Default")
      (node (ref "U1") (pin "P$5") (pinfunction "DCD_P$5") (pintype "bidirectional"))
    )
    (net (code "119") (name "unconnected-(U1-DTR-PadP$3)") (class "Default")
      (node (ref "U1") (pin "P$3") (pinfunction "DTR_P$3") (pintype "bidirectional"))
    )
    (net (code "120") (name "unconnected-(U1-GPIO1-PadP$40)") (class "Default")
      (node (ref "U1") (pin "P$40") (pinfunction "GPIO1_P$40") (pintype "bidirectional"))
    )
    (net (code "121") (name "unconnected-(U1-GPIO2-PadP$41)") (class "Default")
      (node (ref "U1") (pin "P$41") (pinfunction "GPIO2_P$41") (pintype "bidirectional"))
    )
    (net (code "122") (name "unconnected-(U1-GPIO3-PadP$42)") (class "Default")
      (node (ref "U1") (pin "P$42") (pinfunction "GPIO3_P$42") (pintype "bidirectional"))
    )
    (net (code "123") (name "unconnected-(U1-GPIO4-PadP$43)") (class "Default")
      (node (ref "U1") (pin "P$43") (pinfunction "GPIO4_P$43") (pintype "bidirectional"))
    )
    (net (code "124") (name "unconnected-(U1-GPIO6-PadP$47)") (class "Default")
      (node (ref "U1") (pin "P$47") (pinfunction "GPIO6_P$47") (pintype "bidirectional"))
    )
    (net (code "125") (name "unconnected-(U1-GPIO7-PadP$48)") (class "Default")
      (node (ref "U1") (pin "P$48") (pinfunction "GPIO7_P$48") (pintype "bidirectional"))
    )
    (net (code "126") (name "unconnected-(U1-GPIO8{slash}DBG_RXD-PadP$49)") (class "Default")
      (node (ref "U1") (pin "P$49") (pinfunction "GPIO8/DBG_RXD_P$49") (pintype "bidirectional"))
    )
    (net (code "127") (name "unconnected-(U1-GPIO9{slash}DBG_TXD-PadP$50)") (class "Default")
      (node (ref "U1") (pin "P$50") (pinfunction "GPIO9/DBG_TXD_P$50") (pintype "bidirectional"))
    )
    (net (code "128") (name "unconnected-(U1-GPIO11-PadP$67)") (class "Default")
      (node (ref "U1") (pin "P$67") (pinfunction "GPIO11_P$67") (pintype "bidirectional"))
    )
    (net (code "129") (name "unconnected-(U1-GPIO12-PadP$68)") (class "Default")
      (node (ref "U1") (pin "P$68") (pinfunction "GPIO12_P$68") (pintype "bidirectional"))
    )
    (net (code "130") (name "unconnected-(U1-NETLIGHT-PadP$52)") (class "Default")
      (node (ref "U1") (pin "P$52") (pinfunction "NETLIGHT_P$52") (pintype "bidirectional"))
    )
    (net (code "131") (name "unconnected-(U1-PWM1-PadP$35)") (class "Default")
      (node (ref "U1") (pin "P$35") (pinfunction "PWM1_P$35") (pintype "bidirectional"))
    )
    (net (code "132") (name "unconnected-(U1-PWM2-PadP$36)") (class "Default")
      (node (ref "U1") (pin "P$36") (pinfunction "PWM2_P$36") (pintype "bidirectional"))
    )
    (net (code "133") (name "unconnected-(U1-RESET-PadP$16)") (class "Default")
      (node (ref "U1") (pin "P$16") (pinfunction "RESET_P$16") (pintype "bidirectional"))
    )
    (net (code "134") (name "unconnected-(U1-RTS-PadP$8)") (class "Default")
      (node (ref "U1") (pin "P$8") (pinfunction "RTS_P$8") (pintype "bidirectional"))
    )
    (net (code "135") (name "unconnected-(U1-SCL-PadP$38)") (class "Default")
      (node (ref "U1") (pin "P$38") (pinfunction "SCL_P$38") (pintype "bidirectional"))
    )
    (net (code "136") (name "unconnected-(U1-SDA-PadP$37)") (class "Default")
      (node (ref "U1") (pin "P$37") (pinfunction "SDA_P$37") (pintype "bidirectional"))
    )
    (net (code "137") (name "unconnected-(U1-SPI_CLK-PadP$11)") (class "Default")
      (node (ref "U1") (pin "P$11") (pinfunction "SPI_CLK_P$11") (pintype "bidirectional"))
    )
    (net (code "138") (name "unconnected-(U1-SPI_CS-PadP$14)") (class "Default")
      (node (ref "U1") (pin "P$14") (pinfunction "SPI_CS_P$14") (pintype "bidirectional"))
    )
    (net (code "139") (name "unconnected-(U1-SPI_MISO-PadP$13)") (class "Default")
      (node (ref "U1") (pin "P$13") (pinfunction "SPI_MISO_P$13") (pintype "bidirectional"))
    )
    (net (code "140") (name "unconnected-(U1-SPI_MOSI-PadP$12)") (class "Default")
      (node (ref "U1") (pin "P$12") (pinfunction "SPI_MOSI_P$12") (pintype "bidirectional"))
    )
    (net (code "141") (name "unconnected-(U1-USB_DN-PadP$28)") (class "Default")
      (node (ref "U1") (pin "P$28") (pinfunction "USB_DN_P$28") (pintype "bidirectional"))
    )
    (net (code "142") (name "unconnected-(U1-USB_DP-PadP$27)") (class "Default")
      (node (ref "U1") (pin "P$27") (pinfunction "USB_DP_P$27") (pintype "bidirectional"))
    )
    (net (code "143") (name "unconnected-(U1-USIM_DET-PadP$34)") (class "Default")
      (node (ref "U1") (pin "P$34") (pinfunction "USIM_DET_P$34") (pintype "bidirectional"))
    )
    (net (code "144") (name "unconnected-(U1-VBUS-PadP$24)") (class "Default")
      (node (ref "U1") (pin "P$24") (pinfunction "VBUS_P$24") (pintype "bidirectional"))
    )
    (net (code "145") (name "unconnected-(U1-VRTC-PadP$26)") (class "Default")
      (node (ref "U1") (pin "P$26") (pinfunction "VRTC_P$26") (pintype "bidirectional"))
    )
    (net (code "146") (name "unconnected-(U3-INT-Pad7)") (class "Default")
      (node (ref "U3") (pin "7") (pinfunction "INT_7") (pintype "bidirectional"))
    )
    (net (code "147") (name "unconnected-(U4-INT-Pad7)") (class "Default")
      (node (ref "U4") (pin "7") (pinfunction "INT_7") (pintype "bidirectional"))
    )
    (net (code "148") (name "unconnected-(U5-GP5-Pad14)") (class "Default")
      (node (ref "U5") (pin "14") (pinfunction "GP5_14") (pintype "bidirectional"))
    )
    (net (code "149") (name "unconnected-(U5-GP6-Pad15)") (class "Default")
      (node (ref "U5") (pin "15") (pinfunction "GP6_15") (pintype "bidirectional"))
    )
    (net (code "150") (name "unconnected-(U5-GP7-Pad16)") (class "Default")
      (node (ref "U5") (pin "16") (pinfunction "GP7_16") (pintype "bidirectional"))
    )
    (net (code "151") (name "unconnected-(U5-INT-Pad7)") (class "Default")
      (node (ref "U5") (pin "7") (pinfunction "INT_7") (pintype "bidirectional"))
    )
    (net (code "152") (name "unconnected-(U8-VPP-PadC6)") (class "Default")
      (node (ref "U8") (pin "C6") (pinfunction "VPP_C6") (pintype "bidirectional"))
    )
    (net (code "153") (name "unconnected-(U9-X1-PadP$1)") (class "Default")
      (node (ref "U9") (pin "P$1") (pinfunction "X1_P$1") (pintype "bidirectional"))
    )
    (net (code "154") (name "unconnected-(U10-NC-Pad4)") (class "Default")
      (node (ref "U10") (pin "4") (pinfunction "NC_4") (pintype "bidirectional"))
    )
    (net (code "155") (name "unconnected-(U11-NC-Pad2)") (class "Default")
      (node (ref "U11") (pin "2") (pinfunction "NC_2") (pintype "bidirectional"))
    )
    (net (code "156") (name "unconnected-(U11-PG-Pad3)") (class "Default")
      (node (ref "U11") (pin "3") (pinfunction "PG_3") (pintype "bidirectional"))
    )
    (net (code "157") (name "unconnected-(U15-NC-Pad4)") (class "Default")
      (node (ref "U15") (pin "4") (pinfunction "NC_4") (pintype "bidirectional"))
    )
  )
)
